# HIVE_BOARD_CHANNEL_HW.net
KiCad netlist of a schematic drawn in Altium Designer
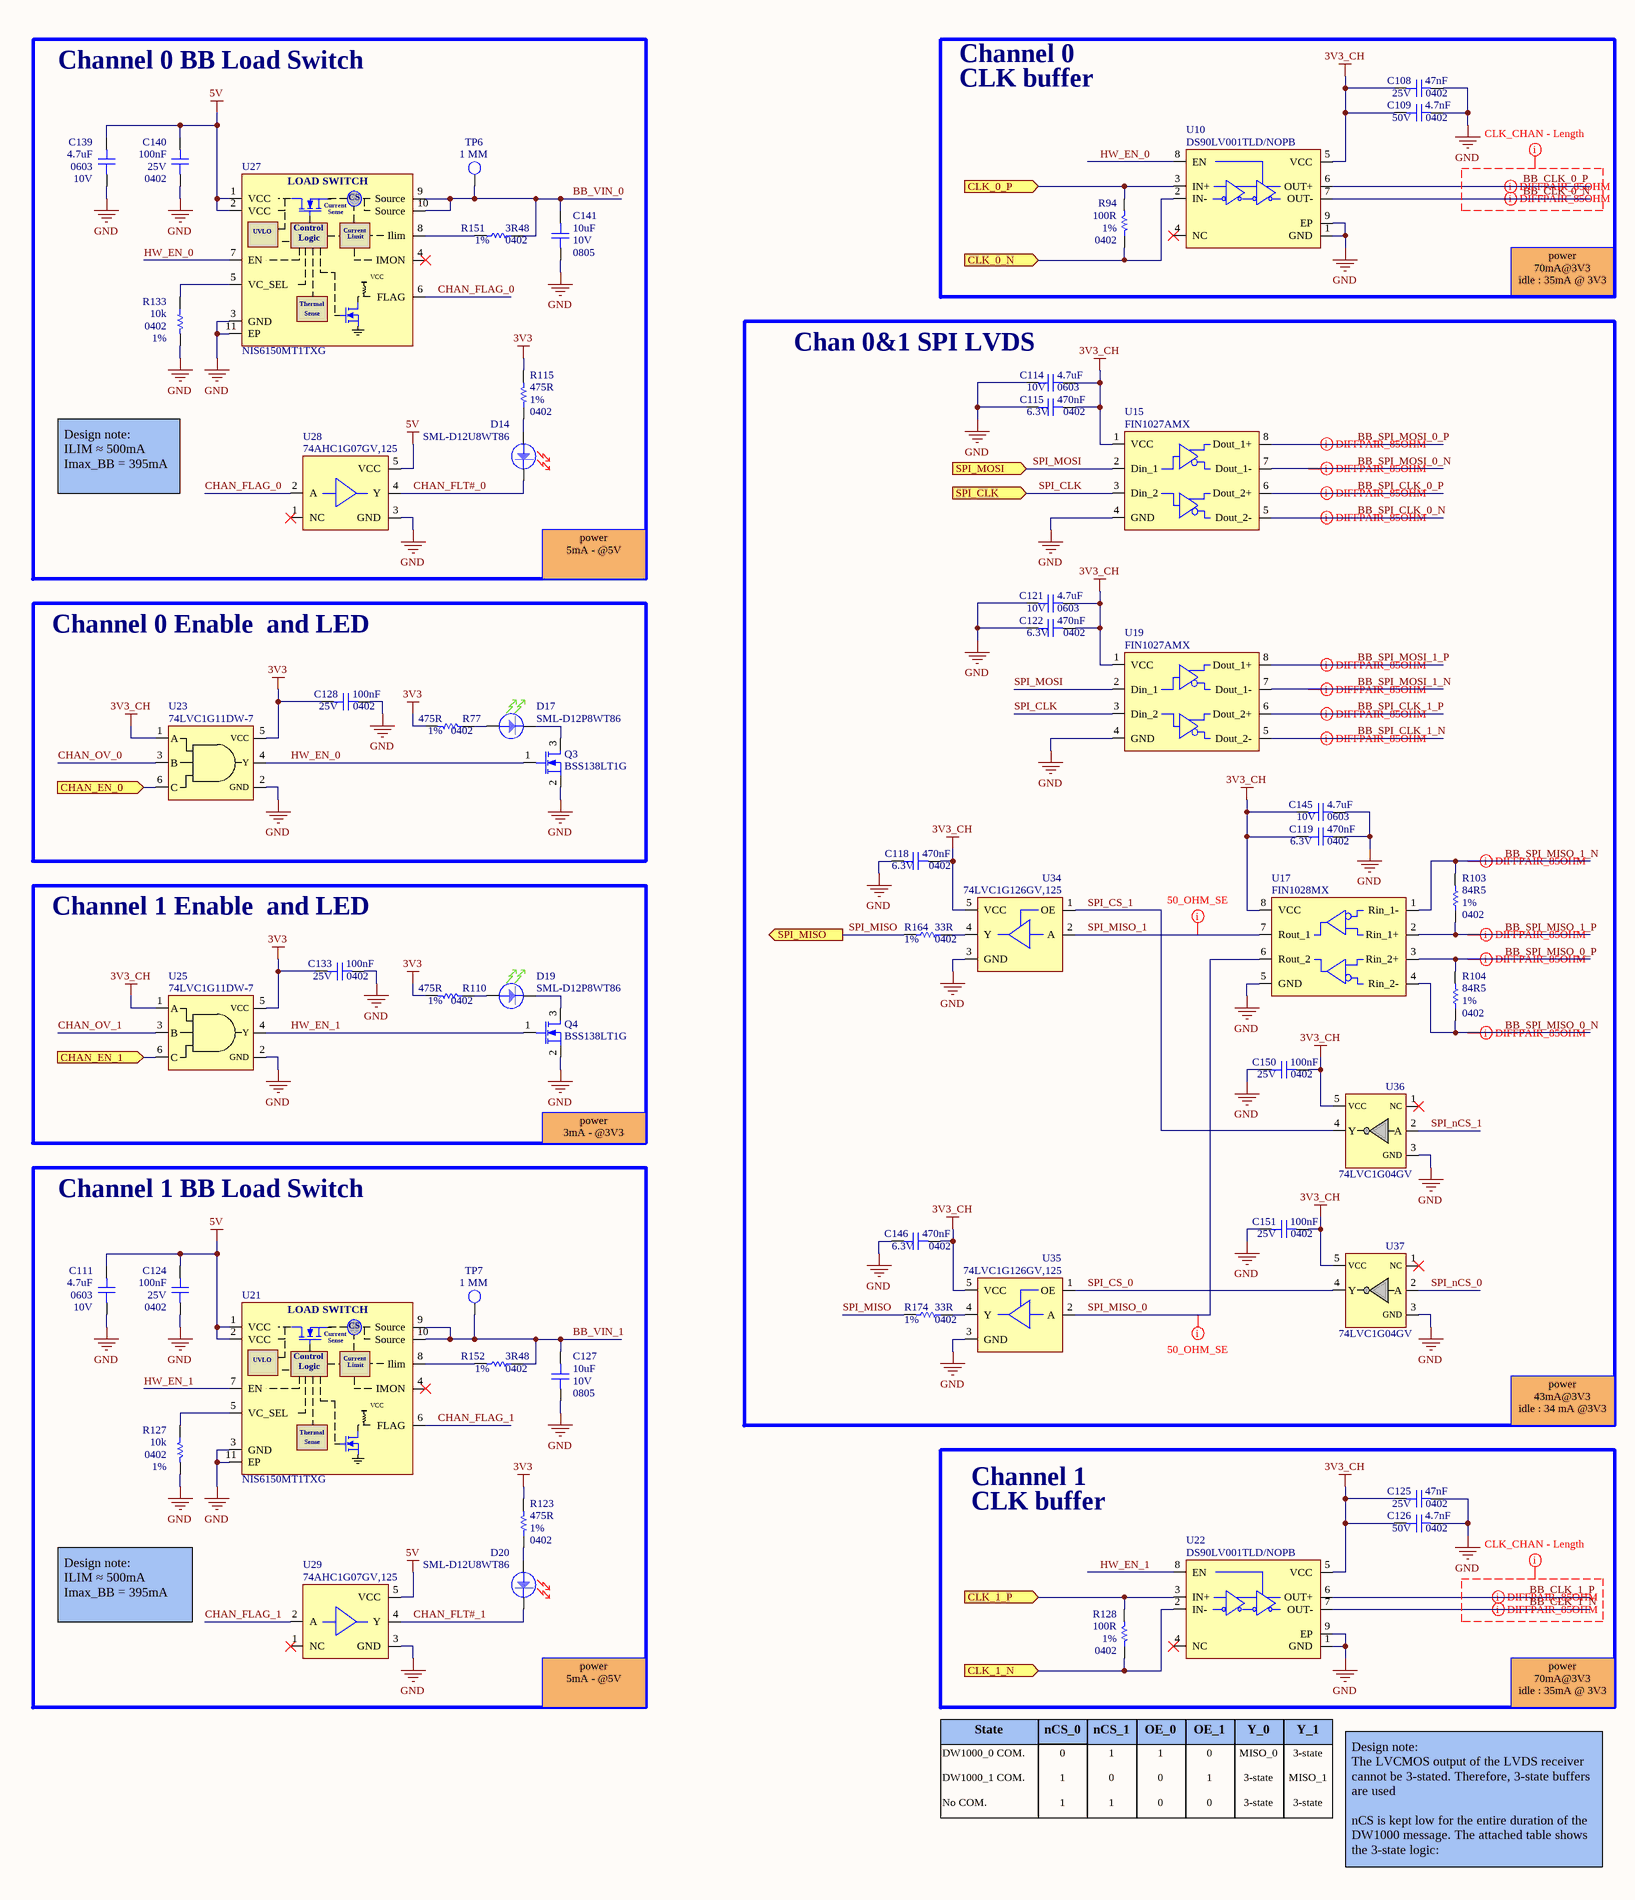
[diagram p0: HIVE_BOARD_CHANNEL_HW.SchDoc, left]
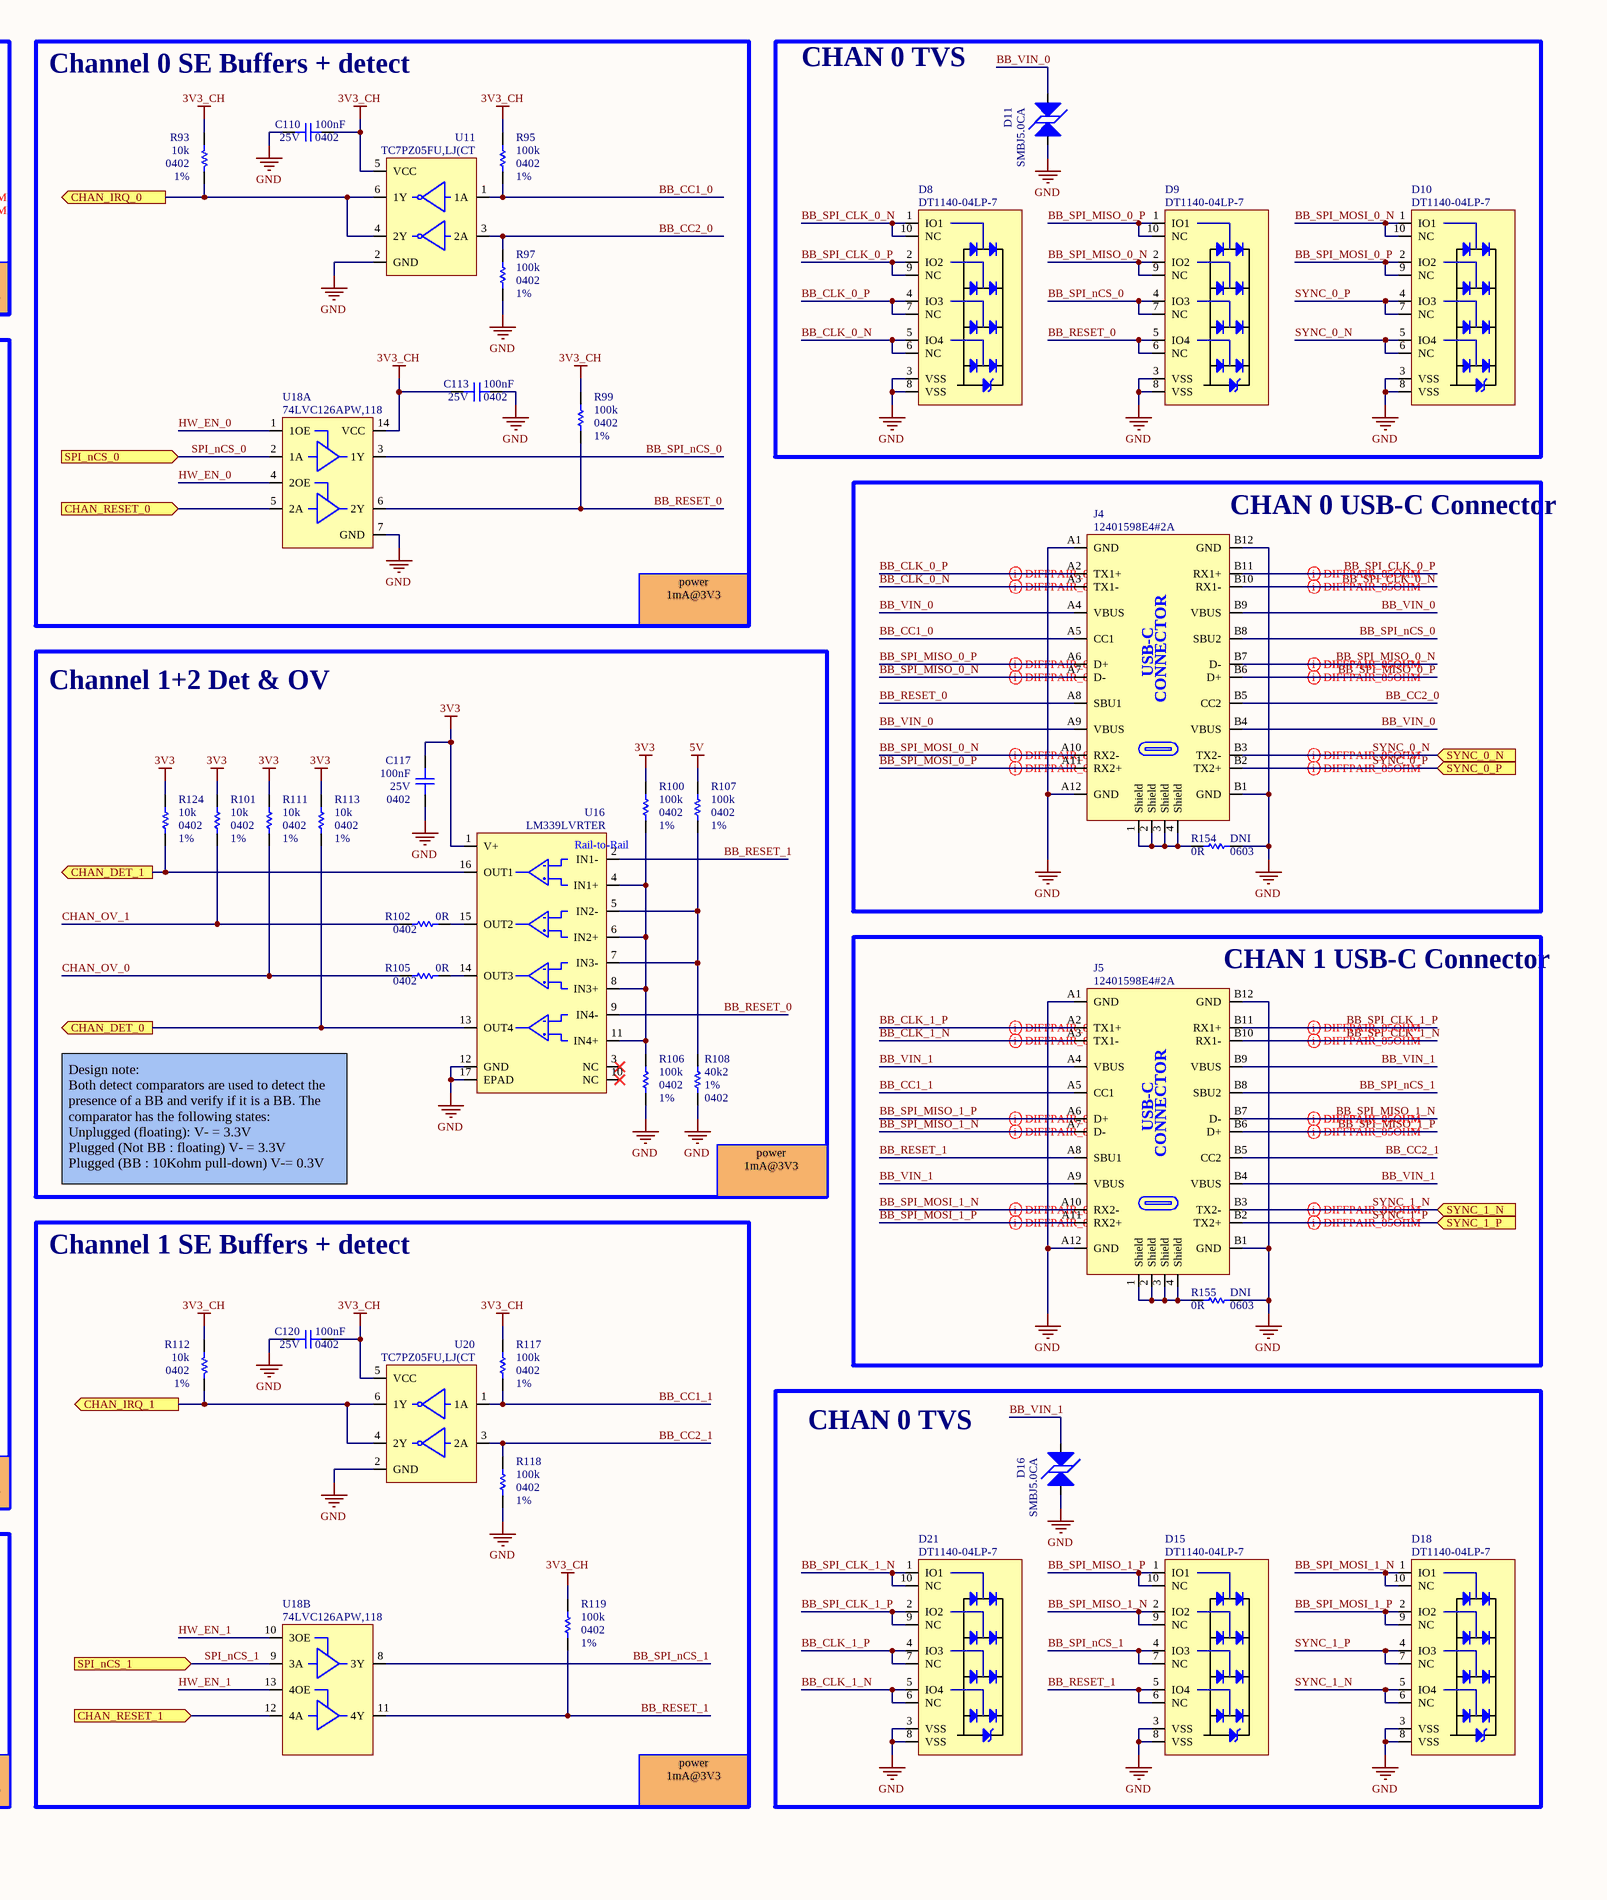
[diagram p1: HIVE_BOARD_CHANNEL_HW.SchDoc, right]

(export (version "E")
  (design (tool "Eeschema 10.0.6"))
  (components
    (comp (ref "C108")
      (value "47nF")
      (footprint "CAP_CER_0402")
      (description "CAP - CER 47nF 25V X7R - 0402")
      (fields
        (field (name "TOLERANCE") "10%")
        (field (name "PACKAGE") "0402")
        (field (name "VOLTAGE RATING") "25V")
        (field (name "Comment") "GRM155R71E473KA88J")
        (field (name "CREATEDBY/DATE") "P. Marcoux 2020-02-05")
        (field (name "VERIFIEDBY") "C.Paulin - 22/04/2020")
      )
      (libsource (lib "GRAMS_MASTER_LIB") (part "CAP_CER_GRM155R71E473KA88J"))
    )
    (comp (ref "C109")
      (value "4.7nF")
      (footprint "CAP_CER_0402")
      (description "CAP - CER 4700PF 50V X7R 0402")
      (fields
        (field (name "TOLERANCE") "±10%")
        (field (name "PACKAGE") "0402")
        (field (name "VOLTAGE RATING") "50V")
        (field (name "Comment") "CL05B472KB5VPNC")
        (field (name "CREATEDBY/DATE") "Philippe Arsenault/ 2021-03-26")
      )
      (libsource (lib "SWARMUS_LIB") (part "CAP_CER_CL05B472KB5VPNC"))
    )
    (comp (ref "C110")
      (value "100nF")
      (footprint "CAP_CER_0402")
      (description "CAP - CER 0.1µF 10% 25V X7R - 0402")
      (fields
        (field (name "TOLERANCE") "10%")
        (field (name "PACKAGE") "0402")
        (field (name "VOLTAGE RATING") "25V")
        (field (name "Comment") "CGA2B3X7R1E104K050BB")
        (field (name "CREATEDBY/DATE") "Nicolas Roy 2018-11-07")
        (field (name "VERIFIEDBY") "Nicolas V. (2019-01-22)")
      )
      (libsource (lib "GRAMS_MASTER_LIB") (part "CAP_CER_CGA2B3X7R1E104K050BB"))
    )
    (comp (ref "C111")
      (value "4.7uF")
      (footprint "CAP_CER_0603")
      (description "4.7µF ±10% 10V Ceramic Capacitor X5R 0603")
      (fields
        (field (name "TOLERANCE") "10%")
        (field (name "PACKAGE") "0603")
        (field (name "VOLTAGE RATING") "10V")
        (field (name "Comment") "CL10A475KP8NNNC")
        (field (name "CREATEDBY/DATE") "Hubert Dube - 25/02/2021")
        (field (name "VERIFIEDBY") "Philippe Arsenault/2021-03-14")
      )
      (libsource (lib "SWARMUS_LIB") (part "CAP_CER_CL10A475KP8NNNC"))
    )
    (comp (ref "C113")
      (value "100nF")
      (footprint "CAP_CER_0402")
      (description "CAP - CER 0.1µF 10% 25V X7R - 0402")
      (fields
        (field (name "TOLERANCE") "10%")
        (field (name "PACKAGE") "0402")
        (field (name "VOLTAGE RATING") "25V")
        (field (name "Comment") "CGA2B3X7R1E104K050BB")
        (field (name "CREATEDBY/DATE") "Nicolas Roy 2018-11-07")
        (field (name "VERIFIEDBY") "Nicolas V. (2019-01-22)")
      )
      (libsource (lib "GRAMS_MASTER_LIB") (part "CAP_CER_CGA2B3X7R1E104K050BB"))
    )
    (comp (ref "C114")
      (value "4.7uF")
      (footprint "CAP_CER_0603")
      (description "4.7µF ±10% 10V Ceramic Capacitor X5R 0603")
      (fields
        (field (name "TOLERANCE") "10%")
        (field (name "PACKAGE") "0603")
        (field (name "VOLTAGE RATING") "10V")
        (field (name "Comment") "CL10A475KP8NNNC")
        (field (name "CREATEDBY/DATE") "Hubert Dube - 25/02/2021")
        (field (name "VERIFIEDBY") "Philippe Arsenault/2021-03-14")
      )
      (libsource (lib "SWARMUS_LIB") (part "CAP_CER_CL10A475KP8NNNC"))
    )
    (comp (ref "C115")
      (value "470nF")
      (footprint "CAP_CER_0402")
      (description "CAP - CER 470nF 6.3V X7R - 0402")
      (fields
        (field (name "TOLERANCE") "10%")
        (field (name "PACKAGE") "0402")
        (field (name "VOLTAGE RATING") "6.3V")
        (field (name "Comment") "JMK105B7474KVHF")
        (field (name "CREATEDBY/DATE") "Nicolas (2019-06-21)")
        (field (name "VERIFIEDBY") "Nicolas V. (2019-06-21)")
      )
      (libsource (lib "GRAMS_MASTER_LIB") (part "CAP_CER_JMK105B7474KVHF"))
    )
    (comp (ref "C117")
      (value "100nF")
      (footprint "CAP_CER_0402")
      (description "CAP - CER 0.1µF 10% 25V X7R - 0402")
      (fields
        (field (name "TOLERANCE") "10%")
        (field (name "PACKAGE") "0402")
        (field (name "VOLTAGE RATING") "25V")
        (field (name "Comment") "CGA2B3X7R1E104K050BB")
        (field (name "CREATEDBY/DATE") "Nicolas Roy 2018-11-07")
        (field (name "VERIFIEDBY") "Nicolas V. (2019-01-22)")
      )
      (libsource (lib "GRAMS_MASTER_LIB") (part "CAP_CER_CGA2B3X7R1E104K050BB"))
    )
    (comp (ref "C118")
      (value "470nF")
      (footprint "CAP_CER_0402")
      (description "CAP - CER 470nF 6.3V X7R - 0402")
      (fields
        (field (name "TOLERANCE") "10%")
        (field (name "PACKAGE") "0402")
        (field (name "VOLTAGE RATING") "6.3V")
        (field (name "Comment") "JMK105B7474KVHF")
        (field (name "CREATEDBY/DATE") "Nicolas (2019-06-21)")
        (field (name "VERIFIEDBY") "Nicolas V. (2019-06-21)")
      )
      (libsource (lib "GRAMS_MASTER_LIB") (part "CAP_CER_JMK105B7474KVHF"))
    )
    (comp (ref "C119")
      (value "470nF")
      (footprint "CAP_CER_0402")
      (description "CAP - CER 470nF 6.3V X7R - 0402")
      (fields
        (field (name "TOLERANCE") "10%")
        (field (name "PACKAGE") "0402")
        (field (name "VOLTAGE RATING") "6.3V")
        (field (name "Comment") "JMK105B7474KVHF")
        (field (name "CREATEDBY/DATE") "Nicolas (2019-06-21)")
        (field (name "VERIFIEDBY") "Nicolas V. (2019-06-21)")
      )
      (libsource (lib "GRAMS_MASTER_LIB") (part "CAP_CER_JMK105B7474KVHF"))
    )
    (comp (ref "C120")
      (value "100nF")
      (footprint "CAP_CER_0402")
      (description "CAP - CER 0.1µF 10% 25V X7R - 0402")
      (fields
        (field (name "TOLERANCE") "10%")
        (field (name "PACKAGE") "0402")
        (field (name "VOLTAGE RATING") "25V")
        (field (name "Comment") "CGA2B3X7R1E104K050BB")
        (field (name "CREATEDBY/DATE") "Nicolas Roy 2018-11-07")
        (field (name "VERIFIEDBY") "Nicolas V. (2019-01-22)")
      )
      (libsource (lib "GRAMS_MASTER_LIB") (part "CAP_CER_CGA2B3X7R1E104K050BB"))
    )
    (comp (ref "C121")
      (value "4.7uF")
      (footprint "CAP_CER_0603")
      (description "4.7µF ±10% 10V Ceramic Capacitor X5R 0603")
      (fields
        (field (name "TOLERANCE") "10%")
        (field (name "PACKAGE") "0603")
        (field (name "VOLTAGE RATING") "10V")
        (field (name "Comment") "CL10A475KP8NNNC")
        (field (name "CREATEDBY/DATE") "Hubert Dube - 25/02/2021")
        (field (name "VERIFIEDBY") "Philippe Arsenault/2021-03-14")
      )
      (libsource (lib "SWARMUS_LIB") (part "CAP_CER_CL10A475KP8NNNC"))
    )
    (comp (ref "C122")
      (value "470nF")
      (footprint "CAP_CER_0402")
      (description "CAP - CER 470nF 6.3V X7R - 0402")
      (fields
        (field (name "TOLERANCE") "10%")
        (field (name "PACKAGE") "0402")
        (field (name "VOLTAGE RATING") "6.3V")
        (field (name "Comment") "JMK105B7474KVHF")
        (field (name "CREATEDBY/DATE") "Nicolas (2019-06-21)")
        (field (name "VERIFIEDBY") "Nicolas V. (2019-06-21)")
      )
      (libsource (lib "GRAMS_MASTER_LIB") (part "CAP_CER_JMK105B7474KVHF"))
    )
    (comp (ref "C124")
      (value "100nF")
      (footprint "CAP_CER_0402")
      (description "CAP - CER 0.1µF 10% 25V X7R - 0402")
      (fields
        (field (name "TOLERANCE") "10%")
        (field (name "PACKAGE") "0402")
        (field (name "VOLTAGE RATING") "25V")
        (field (name "Comment") "CGA2B3X7R1E104K050BB")
        (field (name "CREATEDBY/DATE") "Nicolas Roy 2018-11-07")
        (field (name "VERIFIEDBY") "Nicolas V. (2019-01-22)")
      )
      (libsource (lib "GRAMS_MASTER_LIB") (part "CAP_CER_CGA2B3X7R1E104K050BB"))
    )
    (comp (ref "C125")
      (value "47nF")
      (footprint "CAP_CER_0402")
      (description "CAP - CER 47nF 25V X7R - 0402")
      (fields
        (field (name "TOLERANCE") "10%")
        (field (name "PACKAGE") "0402")
        (field (name "VOLTAGE RATING") "25V")
        (field (name "Comment") "GRM155R71E473KA88J")
        (field (name "CREATEDBY/DATE") "P. Marcoux 2020-02-05")
        (field (name "VERIFIEDBY") "C.Paulin - 22/04/2020")
      )
      (libsource (lib "GRAMS_MASTER_LIB") (part "CAP_CER_GRM155R71E473KA88J"))
    )
    (comp (ref "C126")
      (value "4.7nF")
      (footprint "CAP_CER_0402")
      (description "CAP - CER 4700PF 50V X7R 0402")
      (fields
        (field (name "TOLERANCE") "±10%")
        (field (name "PACKAGE") "0402")
        (field (name "VOLTAGE RATING") "50V")
        (field (name "Comment") "CL05B472KB5VPNC")
        (field (name "CREATEDBY/DATE") "Philippe Arsenault/ 2021-03-26")
      )
      (libsource (lib "SWARMUS_LIB") (part "CAP_CER_CL05B472KB5VPNC"))
    )
    (comp (ref "C127")
      (value "10uF")
      (footprint "CAP_CER_0805")
      (description "CAP - CER 10UF 10% 10V X5R - 0805")
      (fields
        (field (name "TOLERANCE") "10%")
        (field (name "PACKAGE") "0805")
        (field (name "VOLTAGE RATING") "10V")
        (field (name "Comment") "LMK212BJ106KG-T")
        (field (name "CREATEDBY/DATE") "Caroline Paulin / 25 juillet 2018")
        (field (name "VERIFIEDBY") "Nicolas V. (2019-01-22)")
      )
      (libsource (lib "GRAMS_MASTER_LIB") (part "CAP_CER_LMK212BJ106KG-T"))
    )
    (comp (ref "C128")
      (value "100nF")
      (footprint "CAP_CER_0402")
      (description "CAP - CER 0.1µF 10% 25V X7R - 0402")
      (fields
        (field (name "TOLERANCE") "10%")
        (field (name "PACKAGE") "0402")
        (field (name "VOLTAGE RATING") "25V")
        (field (name "Comment") "CGA2B3X7R1E104K050BB")
        (field (name "CREATEDBY/DATE") "Nicolas Roy 2018-11-07")
        (field (name "VERIFIEDBY") "Nicolas V. (2019-01-22)")
      )
      (libsource (lib "GRAMS_MASTER_LIB") (part "CAP_CER_CGA2B3X7R1E104K050BB"))
    )
    (comp (ref "C133")
      (value "100nF")
      (footprint "CAP_CER_0402")
      (description "CAP - CER 0.1µF 10% 25V X7R - 0402")
      (fields
        (field (name "TOLERANCE") "10%")
        (field (name "PACKAGE") "0402")
        (field (name "VOLTAGE RATING") "25V")
        (field (name "Comment") "CGA2B3X7R1E104K050BB")
        (field (name "CREATEDBY/DATE") "Nicolas Roy 2018-11-07")
        (field (name "VERIFIEDBY") "Nicolas V. (2019-01-22)")
      )
      (libsource (lib "GRAMS_MASTER_LIB") (part "CAP_CER_CGA2B3X7R1E104K050BB"))
    )
    (comp (ref "C139")
      (value "4.7uF")
      (footprint "CAP_CER_0603")
      (description "4.7µF ±10% 10V Ceramic Capacitor X5R 0603")
      (fields
        (field (name "TOLERANCE") "10%")
        (field (name "PACKAGE") "0603")
        (field (name "VOLTAGE RATING") "10V")
        (field (name "Comment") "CL10A475KP8NNNC")
        (field (name "CREATEDBY/DATE") "Hubert Dube - 25/02/2021")
        (field (name "VERIFIEDBY") "Philippe Arsenault/2021-03-14")
      )
      (libsource (lib "SWARMUS_LIB") (part "CAP_CER_CL10A475KP8NNNC"))
    )
    (comp (ref "C140")
      (value "100nF")
      (footprint "CAP_CER_0402")
      (description "CAP - CER 0.1µF 10% 25V X7R - 0402")
      (fields
        (field (name "TOLERANCE") "10%")
        (field (name "PACKAGE") "0402")
        (field (name "VOLTAGE RATING") "25V")
        (field (name "Comment") "CGA2B3X7R1E104K050BB")
        (field (name "CREATEDBY/DATE") "Nicolas Roy 2018-11-07")
        (field (name "VERIFIEDBY") "Nicolas V. (2019-01-22)")
      )
      (libsource (lib "GRAMS_MASTER_LIB") (part "CAP_CER_CGA2B3X7R1E104K050BB"))
    )
    (comp (ref "C141")
      (value "10uF")
      (footprint "CAP_CER_0805")
      (description "CAP - CER 10UF 10% 10V X5R - 0805")
      (fields
        (field (name "TOLERANCE") "10%")
        (field (name "PACKAGE") "0805")
        (field (name "VOLTAGE RATING") "10V")
        (field (name "Comment") "LMK212BJ106KG-T")
        (field (name "CREATEDBY/DATE") "Caroline Paulin / 25 juillet 2018")
        (field (name "VERIFIEDBY") "Nicolas V. (2019-01-22)")
      )
      (libsource (lib "GRAMS_MASTER_LIB") (part "CAP_CER_LMK212BJ106KG-T"))
    )
    (comp (ref "C145")
      (value "4.7uF")
      (footprint "CAP_CER_0603")
      (description "4.7µF ±10% 10V Ceramic Capacitor X5R 0603")
      (fields
        (field (name "TOLERANCE") "10%")
        (field (name "PACKAGE") "0603")
        (field (name "VOLTAGE RATING") "10V")
        (field (name "Comment") "CL10A475KP8NNNC")
        (field (name "CREATEDBY/DATE") "Hubert Dube - 25/02/2021")
        (field (name "VERIFIEDBY") "Philippe Arsenault/2021-03-14")
      )
      (libsource (lib "SWARMUS_LIB") (part "CAP_CER_CL10A475KP8NNNC"))
    )
    (comp (ref "C146")
      (value "470nF")
      (footprint "CAP_CER_0402")
      (description "CAP - CER 470nF 6.3V X7R - 0402")
      (fields
        (field (name "TOLERANCE") "10%")
        (field (name "PACKAGE") "0402")
        (field (name "VOLTAGE RATING") "6.3V")
        (field (name "Comment") "JMK105B7474KVHF")
        (field (name "CREATEDBY/DATE") "Nicolas (2019-06-21)")
        (field (name "VERIFIEDBY") "Nicolas V. (2019-06-21)")
      )
      (libsource (lib "GRAMS_MASTER_LIB") (part "CAP_CER_JMK105B7474KVHF"))
    )
    (comp (ref "C150")
      (value "100nF")
      (footprint "CAP_CER_0402")
      (description "CAP - CER 0.1µF 10% 25V X7R - 0402")
      (fields
        (field (name "TOLERANCE") "10%")
        (field (name "PACKAGE") "0402")
        (field (name "VOLTAGE RATING") "25V")
        (field (name "Comment") "CGA2B3X7R1E104K050BB")
        (field (name "CREATEDBY/DATE") "Nicolas Roy 2018-11-07")
        (field (name "VERIFIEDBY") "Nicolas V. (2019-01-22)")
      )
      (libsource (lib "GRAMS_MASTER_LIB") (part "CAP_CER_CGA2B3X7R1E104K050BB"))
    )
    (comp (ref "C151")
      (value "100nF")
      (footprint "CAP_CER_0402")
      (description "CAP - CER 0.1µF 10% 25V X7R - 0402")
      (fields
        (field (name "TOLERANCE") "10%")
        (field (name "PACKAGE") "0402")
        (field (name "VOLTAGE RATING") "25V")
        (field (name "Comment") "CGA2B3X7R1E104K050BB")
        (field (name "CREATEDBY/DATE") "Nicolas Roy 2018-11-07")
        (field (name "VERIFIEDBY") "Nicolas V. (2019-01-22)")
      )
      (libsource (lib "GRAMS_MASTER_LIB") (part "CAP_CER_CGA2B3X7R1E104K050BB"))
    )
    (comp (ref "D8")
      (value "DT1140-04LP-7")
      (footprint "TVS_DATA_DT1140-04LP-7")
      (description "TVS - DIODE 5.5V 10V - 10-UFDFN")
      (fields
        (field (name "CREATEDBY/DATE") "Joël Lemay 2019-11-20")
        (field (name "VERIFIEDBY") "C.Paulin - 21/11/2019")
      )
      (libsource (lib "GRAMS_MASTER_LIB") (part "TVS_DATA_DT1140-04LP-7"))
    )
    (comp (ref "D9")
      (value "DT1140-04LP-7")
      (footprint "TVS_DATA_DT1140-04LP-7")
      (description "TVS - DIODE 5.5V 10V - 10-UFDFN")
      (fields
        (field (name "CREATEDBY/DATE") "Joël Lemay 2019-11-20")
        (field (name "VERIFIEDBY") "C.Paulin - 21/11/2019")
      )
      (libsource (lib "GRAMS_MASTER_LIB") (part "TVS_DATA_DT1140-04LP-7"))
    )
    (comp (ref "D10")
      (value "DT1140-04LP-7")
      (footprint "TVS_DATA_DT1140-04LP-7")
      (description "TVS - DIODE 5.5V 10V - 10-UFDFN")
      (fields
        (field (name "CREATEDBY/DATE") "Joël Lemay 2019-11-20")
        (field (name "VERIFIEDBY") "C.Paulin - 21/11/2019")
      )
      (libsource (lib "GRAMS_MASTER_LIB") (part "TVS_DATA_DT1140-04LP-7"))
    )
    (comp (ref "D11")
      (value "SMBJ5.0CA")
      (footprint "TVS_PWR_SMBJ5.0CA")
      (description "TVS - BIDIR 5V 9.2V 600W - DO214AA")
      (fields
        (field (name "CREATEDBY/DATE") "Jonathan Bouchard - 2019-03-22")
        (field (name "VERIFIEDBY") "Nicolas V. (2019-05-06)")
      )
      (libsource (lib "GRAMS_MASTER_LIB") (part "TVS_PWR_SMBJ5.0CA"))
    )
    (comp (ref "D14")
      (value "SML-D12U8WT86")
      (footprint "LED_SML-D12U8WT86")
      (description "LED - RED DIFFUSED 0603 SMD - 0603")
      (fields
        (field (name "CREATEDBY/DATE") "Olivier Bernard / 01/02/2018")
        (field (name "VERIFIEDBY") "Caroline Paulin / 6 juillet 2018")
      )
      (libsource (lib "GRAMS_MASTER_LIB") (part "LED_SML-D12U8WT86"))
    )
    (comp (ref "D15")
      (value "DT1140-04LP-7")
      (footprint "TVS_DATA_DT1140-04LP-7")
      (description "TVS - DIODE 5.5V 10V - 10-UFDFN")
      (fields
        (field (name "CREATEDBY/DATE") "Joël Lemay 2019-11-20")
        (field (name "VERIFIEDBY") "C.Paulin - 21/11/2019")
      )
      (libsource (lib "GRAMS_MASTER_LIB") (part "TVS_DATA_DT1140-04LP-7"))
    )
    (comp (ref "D16")
      (value "SMBJ5.0CA")
      (footprint "TVS_PWR_SMBJ5.0CA")
      (description "TVS - BIDIR 5V 9.2V 600W - DO214AA")
      (fields
        (field (name "CREATEDBY/DATE") "Jonathan Bouchard - 2019-03-22")
        (field (name "VERIFIEDBY") "Nicolas V. (2019-05-06)")
      )
      (libsource (lib "GRAMS_MASTER_LIB") (part "TVS_PWR_SMBJ5.0CA"))
    )
    (comp (ref "D17")
      (value "SML-D12P8WT86")
      (footprint "LED_SML-D12P8WT86")
      (description "LED - GREEN DIFFUSED 0603 SMD - 0603")
      (fields
        (field (name "CREATEDBY/DATE") "Keven Deslandes - 2018/11/21")
        (field (name "VERIFIEDBY") "Caroline Paulin - 13 février 2019")
      )
      (libsource (lib "GRAMS_MASTER_LIB") (part "LED_SML-D12P8WT86"))
    )
    (comp (ref "D18")
      (value "DT1140-04LP-7")
      (footprint "TVS_DATA_DT1140-04LP-7")
      (description "TVS - DIODE 5.5V 10V - 10-UFDFN")
      (fields
        (field (name "CREATEDBY/DATE") "Joël Lemay 2019-11-20")
        (field (name "VERIFIEDBY") "C.Paulin - 21/11/2019")
      )
      (libsource (lib "GRAMS_MASTER_LIB") (part "TVS_DATA_DT1140-04LP-7"))
    )
    (comp (ref "D19")
      (value "SML-D12P8WT86")
      (footprint "LED_SML-D12P8WT86")
      (description "LED - GREEN DIFFUSED 0603 SMD - 0603")
      (fields
        (field (name "CREATEDBY/DATE") "Keven Deslandes - 2018/11/21")
        (field (name "VERIFIEDBY") "Caroline Paulin - 13 février 2019")
      )
      (libsource (lib "GRAMS_MASTER_LIB") (part "LED_SML-D12P8WT86"))
    )
    (comp (ref "D20")
      (value "SML-D12U8WT86")
      (footprint "LED_SML-D12U8WT86")
      (description "LED - RED DIFFUSED 0603 SMD - 0603")
      (fields
        (field (name "CREATEDBY/DATE") "Olivier Bernard / 01/02/2018")
        (field (name "VERIFIEDBY") "Caroline Paulin / 6 juillet 2018")
      )
      (libsource (lib "GRAMS_MASTER_LIB") (part "LED_SML-D12U8WT86"))
    )
    (comp (ref "D21")
      (value "DT1140-04LP-7")
      (footprint "TVS_DATA_DT1140-04LP-7")
      (description "TVS - DIODE 5.5V 10V - 10-UFDFN")
      (fields
        (field (name "CREATEDBY/DATE") "Joël Lemay 2019-11-20")
        (field (name "VERIFIEDBY") "C.Paulin - 21/11/2019")
      )
      (libsource (lib "GRAMS_MASTER_LIB") (part "TVS_DATA_DT1140-04LP-7"))
    )
    (comp (ref "J4")
      (value "12401598E4#2A")
      (footprint "CON_USB_3.2_TypeC_12401598E4#2A")
      (description "CON_USB - USB 3.2 Gen 2 (USB 3.1 Gen 2, Superspeed + (USB 3.1)) 24 pos Receptacle - R/A")
      (fields
        (field (name "CREATEDBY/DATE") "Louis-Daniel Gaulin / 07-04-2021")
        (field (name "VERIFIEDBY") "Philippe Arsenault/2021-04-08")
      )
      (libsource (lib "SWARMUS_LIB") (part "CON_USB_3.2_TypeC_12401598E4#2A"))
    )
    (comp (ref "J5")
      (value "12401598E4#2A")
      (footprint "CON_USB_3.2_TypeC_12401598E4#2A")
      (description "CON_USB - USB 3.2 Gen 2 (USB 3.1 Gen 2, Superspeed + (USB 3.1)) 24 pos Receptacle - R/A")
      (fields
        (field (name "CREATEDBY/DATE") "Louis-Daniel Gaulin / 07-04-2021")
        (field (name "VERIFIEDBY") "Philippe Arsenault/2021-04-08")
      )
      (libsource (lib "SWARMUS_LIB") (part "CON_USB_3.2_TypeC_12401598E4#2A"))
    )
    (comp (ref "Q3")
      (value "BSS138LT1G")
      (footprint "TRX_NMOS_BSS138LT1G")
      (description "TRX - NMOS - 50V 200MA - SOT−23-3")
      (fields
        (field (name "CREATEDBY/DATE") "Joel Lemay 2018-06-15")
        (field (name "VERIFIEDBY") "Caroline Paulin - 6 sept 2018")
      )
      (libsource (lib "GRAMS_MASTER_LIB") (part "TRX_NMOS_BSS138LT1G"))
    )
    (comp (ref "Q4")
      (value "BSS138LT1G")
      (footprint "TRX_NMOS_BSS138LT1G")
      (description "TRX - NMOS - 50V 200MA - SOT−23-3")
      (fields
        (field (name "CREATEDBY/DATE") "Joel Lemay 2018-06-15")
        (field (name "VERIFIEDBY") "Caroline Paulin - 6 sept 2018")
      )
      (libsource (lib "GRAMS_MASTER_LIB") (part "TRX_NMOS_BSS138LT1G"))
    )
    (comp (ref "R77")
      (value "475R")
      (footprint "RES_0402")
      (description "RES - 475R 1% 1/10W- 0402")
      (fields
        (field (name "TOLERANCE") "1%")
        (field (name "PACKAGE") "0402")
        (field (name "Comment") "ERJ-2RKF4750X")
        (field (name "CREATEDBY/DATE") "Keven Deslandes 2018-10-17")
        (field (name "VERIFIEDBY") "Carolilne Paulin - 18/12/2018")
      )
      (libsource (lib "GRAMS_MASTER_LIB") (part "RES_ERJ-2RKF4750X"))
    )
    (comp (ref "R93")
      (value "10k")
      (footprint "RES_0402")
      (description "RES - 10K OHMS 1% 1/16W - 0402")
      (fields
        (field (name "TOLERANCE") "1%")
        (field (name "PACKAGE") "0402")
        (field (name "Comment") "RC0402FR-0710KL")
        (field (name "CREATEDBY/DATE") "Nicolas V. (2018-11-20)")
        (field (name "VERIFIEDBY") "Nicolas V. (2018-11-20)")
      )
      (libsource (lib "GRAMS_MASTER_LIB") (part "RES_RC0402FR-0710KL"))
    )
    (comp (ref "R94")
      (value "100R")
      (footprint "RES_0402")
      (description "RES - 100R OHM 1% 1/16W - 0402")
      (fields
        (field (name "TOLERANCE") "1%")
        (field (name "PACKAGE") "0402")
        (field (name "Comment") "RC0402FR-07100RP")
        (field (name "CREATEDBY/DATE") "Jonathan Bouchard 2018-07-05")
        (field (name "VERIFIEDBY") "Arnaud Samson 16-07-18")
      )
      (libsource (lib "GRAMS_MASTER_LIB") (part "RES_RC0402FR-07100RP"))
    )
    (comp (ref "R95")
      (value "100k")
      (footprint "RES_0402")
      (description "RES - 100K 1% 1/16W - 0402")
      (fields
        (field (name "TOLERANCE") "1%")
        (field (name "PACKAGE") "0402")
        (field (name "Comment") "RC0402FR-07100KL")
        (field (name "CREATEDBY/DATE") "Keven Deslandes 2018-10-19")
        (field (name "VERIFIEDBY") "Caroline Paulin - 18/12/2018")
      )
      (libsource (lib "GRAMS_MASTER_LIB") (part "RES_RC0402FR-07100KL"))
    )
    (comp (ref "R97")
      (value "100k")
      (footprint "RES_0402")
      (description "RES - 100K 1% 1/16W - 0402")
      (fields
        (field (name "TOLERANCE") "1%")
        (field (name "PACKAGE") "0402")
        (field (name "Comment") "RC0402FR-07100KL")
        (field (name "CREATEDBY/DATE") "Keven Deslandes 2018-10-19")
        (field (name "VERIFIEDBY") "Caroline Paulin - 18/12/2018")
      )
      (libsource (lib "GRAMS_MASTER_LIB") (part "RES_RC0402FR-07100KL"))
    )
    (comp (ref "R99")
      (value "100k")
      (footprint "RES_0402")
      (description "RES - 100K 1% 1/16W - 0402")
      (fields
        (field (name "TOLERANCE") "1%")
        (field (name "PACKAGE") "0402")
        (field (name "Comment") "RC0402FR-07100KL")
        (field (name "CREATEDBY/DATE") "Keven Deslandes 2018-10-19")
        (field (name "VERIFIEDBY") "Caroline Paulin - 18/12/2018")
      )
      (libsource (lib "GRAMS_MASTER_LIB") (part "RES_RC0402FR-07100KL"))
    )
    (comp (ref "R100")
      (value "100k")
      (footprint "RES_0402")
      (description "RES - 100K 1% 1/16W - 0402")
      (fields
        (field (name "TOLERANCE") "1%")
        (field (name "PACKAGE") "0402")
        (field (name "Comment") "RC0402FR-07100KL")
        (field (name "CREATEDBY/DATE") "Keven Deslandes 2018-10-19")
        (field (name "VERIFIEDBY") "Caroline Paulin - 18/12/2018")
      )
      (libsource (lib "GRAMS_MASTER_LIB") (part "RES_RC0402FR-07100KL"))
    )
    (comp (ref "R101")
      (value "10k")
      (footprint "RES_0402")
      (description "RES - 10K OHMS 1% 1/16W - 0402")
      (fields
        (field (name "TOLERANCE") "1%")
        (field (name "PACKAGE") "0402")
        (field (name "Comment") "RC0402FR-0710KL")
        (field (name "CREATEDBY/DATE") "Nicolas V. (2018-11-20)")
        (field (name "VERIFIEDBY") "Nicolas V. (2018-11-20)")
      )
      (libsource (lib "GRAMS_MASTER_LIB") (part "RES_RC0402FR-0710KL"))
    )
    (comp (ref "R102")
      (value "0R")
      (footprint "RES_0402")
      (description "RES - 0R 1/16W 1A  - 0402")
      (fields
        (field (name "PACKAGE") "0402")
        (field (name "Comment") "RC0402FR-070RL")
        (field (name "CREATEDBY/DATE") "Keven Deslandes 2018-09-12")
        (field (name "VERIFIEDBY") "Caroline Paulin - 27 fév 2019")
      )
      (libsource (lib "GRAMS_MASTER_LIB") (part "RES_RC0402FR-070RL"))
    )
    (comp (ref "R103")
      (value "84R5")
      (footprint "RES_0402")
      (description "RES - 84R5 1% 1/16W - 0402")
      (fields
        (field (name "TOLERANCE") "1%")
        (field (name "PACKAGE") "0402")
        (field (name "Comment") "RC0402FR-0784R5L")
        (field (name "CREATEDBY/DATE") "Philippe Arsenault/ 2021-03-31")
      )
      (libsource (lib "SWARMUS_LIB") (part "RES_RC0402FR-0784R5L"))
    )
    (comp (ref "R104")
      (value "84R5")
      (footprint "RES_0402")
      (description "RES - 84R5 1% 1/16W - 0402")
      (fields
        (field (name "TOLERANCE") "1%")
        (field (name "PACKAGE") "0402")
        (field (name "Comment") "RC0402FR-0784R5L")
        (field (name "CREATEDBY/DATE") "Philippe Arsenault/ 2021-03-31")
      )
      (libsource (lib "SWARMUS_LIB") (part "RES_RC0402FR-0784R5L"))
    )
    (comp (ref "R105")
      (value "0R")
      (footprint "RES_0402")
      (description "RES - 0R 1/16W 1A  - 0402")
      (fields
        (field (name "PACKAGE") "0402")
        (field (name "Comment") "RC0402FR-070RL")
        (field (name "CREATEDBY/DATE") "Keven Deslandes 2018-09-12")
        (field (name "VERIFIEDBY") "Caroline Paulin - 27 fév 2019")
      )
      (libsource (lib "GRAMS_MASTER_LIB") (part "RES_RC0402FR-070RL"))
    )
    (comp (ref "R106")
      (value "100k")
      (footprint "RES_0402")
      (description "RES - 100K 1% 1/16W - 0402")
      (fields
        (field (name "TOLERANCE") "1%")
        (field (name "PACKAGE") "0402")
        (field (name "Comment") "RC0402FR-07100KL")
        (field (name "CREATEDBY/DATE") "Keven Deslandes 2018-10-19")
        (field (name "VERIFIEDBY") "Caroline Paulin - 18/12/2018")
      )
      (libsource (lib "GRAMS_MASTER_LIB") (part "RES_RC0402FR-07100KL"))
    )
    (comp (ref "R107")
      (value "100k")
      (footprint "RES_0402")
      (description "RES - 100K 1% 1/16W - 0402")
      (fields
        (field (name "TOLERANCE") "1%")
        (field (name "PACKAGE") "0402")
        (field (name "Comment") "RC0402FR-07100KL")
        (field (name "CREATEDBY/DATE") "Keven Deslandes 2018-10-19")
        (field (name "VERIFIEDBY") "Caroline Paulin - 18/12/2018")
      )
      (libsource (lib "GRAMS_MASTER_LIB") (part "RES_RC0402FR-07100KL"))
    )
    (comp (ref "R108")
      (value "40k2")
      (footprint "RES_0402")
      (description "RES - 40.2K 1% 1/16W - 0402")
      (fields
        (field (name "TOLERANCE") "1%")
        (field (name "PACKAGE") "0402")
        (field (name "Comment") "RC0402FR-0740K2L")
        (field (name "CREATEDBY/DATE") "Raphael Bouchard - 2019-08-09")
        (field (name "VERIFIEDBY") "C.Paulin - 15/08/2019")
      )
      (libsource (lib "GRAMS_MASTER_LIB") (part "RES_RC0402FR-0740K2L"))
    )
    (comp (ref "R110")
      (value "475R")
      (footprint "RES_0402")
      (description "RES - 475R 1% 1/10W- 0402")
      (fields
        (field (name "TOLERANCE") "1%")
        (field (name "PACKAGE") "0402")
        (field (name "Comment") "ERJ-2RKF4750X")
        (field (name "CREATEDBY/DATE") "Keven Deslandes 2018-10-17")
        (field (name "VERIFIEDBY") "Carolilne Paulin - 18/12/2018")
      )
      (libsource (lib "GRAMS_MASTER_LIB") (part "RES_ERJ-2RKF4750X"))
    )
    (comp (ref "R111")
      (value "10k")
      (footprint "RES_0402")
      (description "RES - 10K OHMS 1% 1/16W - 0402")
      (fields
        (field (name "TOLERANCE") "1%")
        (field (name "PACKAGE") "0402")
        (field (name "Comment") "RC0402FR-0710KL")
        (field (name "CREATEDBY/DATE") "Nicolas V. (2018-11-20)")
        (field (name "VERIFIEDBY") "Nicolas V. (2018-11-20)")
      )
      (libsource (lib "GRAMS_MASTER_LIB") (part "RES_RC0402FR-0710KL"))
    )
    (comp (ref "R112")
      (value "10k")
      (footprint "RES_0402")
      (description "RES - 10K OHMS 1% 1/16W - 0402")
      (fields
        (field (name "TOLERANCE") "1%")
        (field (name "PACKAGE") "0402")
        (field (name "Comment") "RC0402FR-0710KL")
        (field (name "CREATEDBY/DATE") "Nicolas V. (2018-11-20)")
        (field (name "VERIFIEDBY") "Nicolas V. (2018-11-20)")
      )
      (libsource (lib "GRAMS_MASTER_LIB") (part "RES_RC0402FR-0710KL"))
    )
    (comp (ref "R113")
      (value "10k")
      (footprint "RES_0402")
      (description "RES - 10K OHMS 1% 1/16W - 0402")
      (fields
        (field (name "TOLERANCE") "1%")
        (field (name "PACKAGE") "0402")
        (field (name "Comment") "RC0402FR-0710KL")
        (field (name "CREATEDBY/DATE") "Nicolas V. (2018-11-20)")
        (field (name "VERIFIEDBY") "Nicolas V. (2018-11-20)")
      )
      (libsource (lib "GRAMS_MASTER_LIB") (part "RES_RC0402FR-0710KL"))
    )
    (comp (ref "R115")
      (value "475R")
      (footprint "RES_0402")
      (description "RES - 475R 1% 1/10W- 0402")
      (fields
        (field (name "TOLERANCE") "1%")
        (field (name "PACKAGE") "0402")
        (field (name "Comment") "ERJ-2RKF4750X")
        (field (name "CREATEDBY/DATE") "Keven Deslandes 2018-10-17")
        (field (name "VERIFIEDBY") "Carolilne Paulin - 18/12/2018")
      )
      (libsource (lib "GRAMS_MASTER_LIB") (part "RES_ERJ-2RKF4750X"))
    )
    (comp (ref "R117")
      (value "100k")
      (footprint "RES_0402")
      (description "RES - 100K 1% 1/16W - 0402")
      (fields
        (field (name "TOLERANCE") "1%")
        (field (name "PACKAGE") "0402")
        (field (name "Comment") "RC0402FR-07100KL")
        (field (name "CREATEDBY/DATE") "Keven Deslandes 2018-10-19")
        (field (name "VERIFIEDBY") "Caroline Paulin - 18/12/2018")
      )
      (libsource (lib "GRAMS_MASTER_LIB") (part "RES_RC0402FR-07100KL"))
    )
    (comp (ref "R118")
      (value "100k")
      (footprint "RES_0402")
      (description "RES - 100K 1% 1/16W - 0402")
      (fields
        (field (name "TOLERANCE") "1%")
        (field (name "PACKAGE") "0402")
        (field (name "Comment") "RC0402FR-07100KL")
        (field (name "CREATEDBY/DATE") "Keven Deslandes 2018-10-19")
        (field (name "VERIFIEDBY") "Caroline Paulin - 18/12/2018")
      )
      (libsource (lib "GRAMS_MASTER_LIB") (part "RES_RC0402FR-07100KL"))
    )
    (comp (ref "R119")
      (value "100k")
      (footprint "RES_0402")
      (description "RES - 100K 1% 1/16W - 0402")
      (fields
        (field (name "TOLERANCE") "1%")
        (field (name "PACKAGE") "0402")
        (field (name "Comment") "RC0402FR-07100KL")
        (field (name "CREATEDBY/DATE") "Keven Deslandes 2018-10-19")
        (field (name "VERIFIEDBY") "Caroline Paulin - 18/12/2018")
      )
      (libsource (lib "GRAMS_MASTER_LIB") (part "RES_RC0402FR-07100KL"))
    )
    (comp (ref "R123")
      (value "475R")
      (footprint "RES_0402")
      (description "RES - 475R 1% 1/10W- 0402")
      (fields
        (field (name "TOLERANCE") "1%")
        (field (name "PACKAGE") "0402")
        (field (name "Comment") "ERJ-2RKF4750X")
        (field (name "CREATEDBY/DATE") "Keven Deslandes 2018-10-17")
        (field (name "VERIFIEDBY") "Carolilne Paulin - 18/12/2018")
      )
      (libsource (lib "GRAMS_MASTER_LIB") (part "RES_ERJ-2RKF4750X"))
    )
    (comp (ref "R124")
      (value "10k")
      (footprint "RES_0402")
      (description "RES - 10K OHMS 1% 1/16W - 0402")
      (fields
        (field (name "TOLERANCE") "1%")
        (field (name "PACKAGE") "0402")
        (field (name "Comment") "RC0402FR-0710KL")
        (field (name "CREATEDBY/DATE") "Nicolas V. (2018-11-20)")
        (field (name "VERIFIEDBY") "Nicolas V. (2018-11-20)")
      )
      (libsource (lib "GRAMS_MASTER_LIB") (part "RES_RC0402FR-0710KL"))
    )
    (comp (ref "R127")
      (value "10k")
      (footprint "RES_0402")
      (description "RES - 10K OHMS 1% 1/16W - 0402")
      (fields
        (field (name "TOLERANCE") "1%")
        (field (name "PACKAGE") "0402")
        (field (name "Comment") "RC0402FR-0710KL")
        (field (name "CREATEDBY/DATE") "Nicolas V. (2018-11-20)")
        (field (name "VERIFIEDBY") "Nicolas V. (2018-11-20)")
      )
      (libsource (lib "GRAMS_MASTER_LIB") (part "RES_RC0402FR-0710KL"))
    )
    (comp (ref "R128")
      (value "100R")
      (footprint "RES_0402")
      (description "RES - 100R OHM 1% 1/16W - 0402")
      (fields
        (field (name "TOLERANCE") "1%")
        (field (name "PACKAGE") "0402")
        (field (name "Comment") "RC0402FR-07100RP")
        (field (name "CREATEDBY/DATE") "Jonathan Bouchard 2018-07-05")
        (field (name "VERIFIEDBY") "Arnaud Samson 16-07-18")
      )
      (libsource (lib "GRAMS_MASTER_LIB") (part "RES_RC0402FR-07100RP"))
    )
    (comp (ref "R133")
      (value "10k")
      (footprint "RES_0402")
      (description "RES - 10K OHMS 1% 1/16W - 0402")
      (fields
        (field (name "TOLERANCE") "1%")
        (field (name "PACKAGE") "0402")
        (field (name "Comment") "RC0402FR-0710KL")
        (field (name "CREATEDBY/DATE") "Nicolas V. (2018-11-20)")
        (field (name "VERIFIEDBY") "Nicolas V. (2018-11-20)")
      )
      (libsource (lib "GRAMS_MASTER_LIB") (part "RES_RC0402FR-0710KL"))
    )
    (comp (ref "R151")
      (value "3R48")
      (footprint "RES_0402")
      (description "RES - 3.48 R ±1% 1/16W -  0402")
      (fields
        (field (name "TOLERANCE") "1%")
        (field (name "PACKAGE") "0402")
        (field (name "Comment") "CRCW04023R48FKED")
        (field (name "CREATEDBY/DATE") "Louis-Daniel Gaulin / 2021-05-01")
        (field (name "VERIFIEDBY") "Philippe Arsenault/2021-05-10")
      )
      (libsource (lib "SWARMUS_LIB") (part "RES_CRCW04023R48FKED"))
    )
    (comp (ref "R152")
      (value "3R48")
      (footprint "RES_0402")
      (description "RES - 3.48 R ±1% 1/16W -  0402")
      (fields
        (field (name "TOLERANCE") "1%")
        (field (name "PACKAGE") "0402")
        (field (name "Comment") "CRCW04023R48FKED")
        (field (name "CREATEDBY/DATE") "Louis-Daniel Gaulin / 2021-05-01")
        (field (name "VERIFIEDBY") "Philippe Arsenault/2021-05-10")
      )
      (libsource (lib "SWARMUS_LIB") (part "RES_CRCW04023R48FKED"))
    )
    (comp (ref "R154")
      (value "0R")
      (footprint "RES_0603")
      (description "RES - 0 ohm jumper 1/10W - 0603")
      (fields
        (field (name "ASSEMBLY NOTE") "DNI")
        (field (name "PACKAGE") "0603")
        (field (name "Comment") "RC0603JR-070RL")
        (field (name "CREATEDBY/DATE") "L-P Gauthier 2018-10-30")
        (field (name "VERIFIEDBY") "Caroline Paulin  - 5/11/2018")
      )
      (libsource (lib "GRAMS_MASTER_LIB") (part "RES_RC0603JR-070RL"))
    )
    (comp (ref "R155")
      (value "0R")
      (footprint "RES_0603")
      (description "RES - 0 ohm jumper 1/10W - 0603")
      (fields
        (field (name "ASSEMBLY NOTE") "DNI")
        (field (name "PACKAGE") "0603")
        (field (name "Comment") "RC0603JR-070RL")
        (field (name "CREATEDBY/DATE") "L-P Gauthier 2018-10-30")
        (field (name "VERIFIEDBY") "Caroline Paulin  - 5/11/2018")
      )
      (libsource (lib "GRAMS_MASTER_LIB") (part "RES_RC0603JR-070RL"))
    )
    (comp (ref "R164")
      (value "33R")
      (footprint "RES_0402")
      (description "RES - 33 OHM 1% 1/16W - 0402")
      (fields
        (field (name "TOLERANCE") "1%")
        (field (name "PACKAGE") "0402")
        (field (name "Comment") "RC0402FR-0733RL")
        (field (name "CREATEDBY/DATE") "Louis-Daniel Gaulin/ 14/01/2020")
        (field (name "VERIFIEDBY") "C.Paulin - 21/01/2020")
      )
      (libsource (lib "GRAMS_MASTER_LIB") (part "RES_RC0402FR-0733RL"))
    )
    (comp (ref "R174")
      (value "33R")
      (footprint "RES_0402")
      (description "RES - 33 OHM 1% 1/16W - 0402")
      (fields
        (field (name "TOLERANCE") "1%")
        (field (name "PACKAGE") "0402")
        (field (name "Comment") "RC0402FR-0733RL")
        (field (name "CREATEDBY/DATE") "Louis-Daniel Gaulin/ 14/01/2020")
        (field (name "VERIFIEDBY") "C.Paulin - 21/01/2020")
      )
      (libsource (lib "GRAMS_MASTER_LIB") (part "RES_RC0402FR-0733RL"))
    )
    (comp (ref "TP6")
      (value "1 MM")
      (footprint "TPO_SMD_ROUND_1MM")
      (description "TPO - TEST POINT ROUND SMD PAD ONLY  - 1 MM")
      (fields
        (field (name "CREATEDBY/DATE") "Jonathan Bouchard 2018-07-17")
        (field (name "VERIFIEDBY") "Arnaud Samson 23-07-18")
      )
      (libsource (lib "GRAMS_MASTER_LIB") (part "TPO_SMD_ROUND_1MM"))
    )
    (comp (ref "TP7")
      (value "1 MM")
      (footprint "TPO_SMD_ROUND_1MM")
      (description "TPO - TEST POINT ROUND SMD PAD ONLY  - 1 MM")
      (fields
        (field (name "CREATEDBY/DATE") "Jonathan Bouchard 2018-07-17")
        (field (name "VERIFIEDBY") "Arnaud Samson 23-07-18")
      )
      (libsource (lib "GRAMS_MASTER_LIB") (part "TPO_SMD_ROUND_1MM"))
    )
    (comp (ref "U10")
      (value "DS90LV001TLD/NOPB")
      (footprint "COM_BUF_DS90LV001TLD/NOPB")
      (description "COM_BUF - ReDriver 1 Channel 800Mbps CML,LVDS,LVPECL to LVDS -  \r\n8-WFDFN EP")
      (fields
        (field (name "CREATEDBY/DATE") "Louis-Daniel Gaulin / 07-04-2021")
        (field (name "VERIFIEDBY") "Philippe Arsenault/2021-04-08")
      )
      (libsource (lib "SWARMUS_LIB") (part "COM_BUF_DS90LV001TLD/NOPB"))
    )
    (comp (ref "U11")
      (value "TC7PZ05FU,LJ(CT")
      (footprint "LOG_BUF_TC7PZ05FU,LJ(CT")
      (description "LOG_BUF - DUAL Buffer inverting Open Drain - SOT-363")
      (fields
        (field (name "CREATEDBY/DATE") "Louis-Daniel Gaulin / 14-04-2021")
        (field (name "VERIFIEDBY") "Philippe Arsenault/2021-04-14")
      )
      (libsource (lib "SWARMUS_LIB") (part "LOG_BUF_TC7PZ05FU,LJ(CT"))
    )
    (comp (ref "U15")
      (value "FIN1027AMX")
      (footprint "COM_XCV_FIN1027AMCOM")
      (description "COM_XCV - 3V3 LVCMOS to LVDS, 2 bits, High-SPEED, DIFF driver - SOIC-8")
      (fields
        (field (name "CREATEDBY/DATE") "Philippe Arsenault/2021-04-01")
        (field (name "VERIFIEDBY") "Louis-Daniel Gaulin - 05/04/2021")
      )
      (libsource (lib "SWARMUS_LIB") (part "COM_XCV_FIN1027AMX"))
    )
    (comp (ref "U16")
      (value "LM339LVRTER")
      (footprint "CMP_LM339LVRTER")
      (description "COMP - Quad Comparator General Purpose Open-Drain, Rail-to-Rail - 16-WQFN (3x3)")
      (fields
        (field (name "CREATEDBY/DATE") "Philippe Arsenault/2021-04-10")
        (field (name "VERIFIEDBY") "Louis-Daniel Gaulin / 14-04-2021")
      )
      (libsource (lib "SWARMUS_LIB") (part "CMP_LM339LVRTER"))
    )
    (comp (ref "U17")
      (value "FIN1028MX")
      (footprint "COM_XCV_FIN1028MX")
      (description "COM_XCV - 3V3 LVDS to LVCMOS, 2 bits, High-SPEED, DIFF receiver - SOIC-8")
      (fields
        (field (name "CREATEDBY/DATE") "Philippe Arsenault/2021-04-01")
        (field (name "VERIFIEDBY") "Louis-Daniel Gaulin - 05/04/2021")
      )
      (libsource (lib "SWARMUS_LIB") (part "COM_XCV_FIN1028MX"))
    )
    (comp (ref "U18")
      (value "74LVC126APW,118")
      (footprint "LOG_BUF_74LVC126APW,118")
      (description "LOG_BUF - Quad Buffer non-inverting 3-States - 14-TSSOP")
      (fields
        (field (name "CREATEDBY/DATE") "Louis-Daniel Gaulin / 11-04-2021")
        (field (name "VERIFIEDBY") "Philippe Arsenault/2021-04-14")
      )
      (libsource (lib "SWARMUS_LIB") (part "LOG_BUF_74LVC126APW,118"))
    )
    (comp (ref "U19")
      (value "FIN1027AMX")
      (footprint "COM_XCV_FIN1027AMCOM")
      (description "COM_XCV - 3V3 LVCMOS to LVDS, 2 bits, High-SPEED, DIFF driver - SOIC-8")
      (fields
        (field (name "CREATEDBY/DATE") "Philippe Arsenault/2021-04-01")
        (field (name "VERIFIEDBY") "Louis-Daniel Gaulin - 05/04/2021")
      )
      (libsource (lib "SWARMUS_LIB") (part "COM_XCV_FIN1027AMX"))
    )
    (comp (ref "U20")
      (value "TC7PZ05FU,LJ(CT")
      (footprint "LOG_BUF_TC7PZ05FU,LJ(CT")
      (description "LOG_BUF - DUAL Buffer inverting Open Drain - SOT-363")
      (fields
        (field (name "CREATEDBY/DATE") "Louis-Daniel Gaulin / 14-04-2021")
        (field (name "VERIFIEDBY") "Philippe Arsenault/2021-04-14")
      )
      (libsource (lib "SWARMUS_LIB") (part "LOG_BUF_TC7PZ05FU,LJ(CT"))
    )
    (comp (ref "U21")
      (value "NIS6150MT1TXG")
      (footprint "POW_NIS6150MT1TXG")
      (description "POW -  Electronic Fuse Regulator 1A -  10-WDFNW")
      (fields
        (field (name "TOLERANCE") "See datasheet")
        (field (name "CREATEDBY/DATE") "Louis-Daniel Gaulin / 29-04-2021")
        (field (name "VERIFIEDBY") "Philippe Arsenault/2021-04-30")
      )
      (libsource (lib "SWARMUS_LIB") (part "POW_NIS6150MT1TXG"))
    )
    (comp (ref "U22")
      (value "DS90LV001TLD/NOPB")
      (footprint "COM_BUF_DS90LV001TLD/NOPB")
      (description "COM_BUF - ReDriver 1 Channel 800Mbps CML,LVDS,LVPECL to LVDS -  \r\n8-WFDFN EP")
      (fields
        (field (name "CREATEDBY/DATE") "Louis-Daniel Gaulin / 07-04-2021")
        (field (name "VERIFIEDBY") "Philippe Arsenault/2021-04-08")
      )
      (libsource (lib "SWARMUS_LIB") (part "COM_BUF_DS90LV001TLD/NOPB"))
    )
    (comp (ref "U23")
      (value "74LVC1G11DW-7")
      (footprint "LOG_AND_74LVC1G11DW-7")
      (description "LOG - AND Gate, 1CH 3-INP - 6-TSSOP")
      (fields
        (field (name "CREATEDBY/DATE") "Louis-Daniel Gaulin / 26-02-2020")
        (field (name "VERIFIEDBY") "C.Paulin - 9/03/2020")
      )
      (libsource (lib "GRAMS_MASTER_LIB") (part "LOG_AND_74LVC1G11DW-7"))
    )
    (comp (ref "U25")
      (value "74LVC1G11DW-7")
      (footprint "LOG_AND_74LVC1G11DW-7")
      (description "LOG - AND Gate, 1CH 3-INP - 6-TSSOP")
      (fields
        (field (name "CREATEDBY/DATE") "Louis-Daniel Gaulin / 26-02-2020")
        (field (name "VERIFIEDBY") "C.Paulin - 9/03/2020")
      )
      (libsource (lib "GRAMS_MASTER_LIB") (part "LOG_AND_74LVC1G11DW-7"))
    )
    (comp (ref "U27")
      (value "NIS6150MT1TXG")
      (footprint "POW_NIS6150MT1TXG")
      (description "POW -  Electronic Fuse Regulator 1A -  10-WDFNW")
      (fields
        (field (name "TOLERANCE") "See datasheet")
        (field (name "CREATEDBY/DATE") "Louis-Daniel Gaulin / 29-04-2021")
        (field (name "VERIFIEDBY") "Philippe Arsenault/2021-04-30")
      )
      (libsource (lib "SWARMUS_LIB") (part "POW_NIS6150MT1TXG"))
    )
    (comp (ref "U28")
      (value "74AHC1G07GV,125")
      (footprint "LOG_BUF_ 74AHC1G07GV,125")
      (description "LOG_BUF - Buffer non-inverting Open Drain - SC-74A")
      (fields
        (field (name "CREATEDBY/DATE") "Louis-Daniel Gaulin / 07-04-2021")
        (field (name "VERIFIEDBY") "Philippe Arsenault/2021-04-08")
      )
      (libsource (lib "SWARMUS_LIB") (part "LOG_BUF_74AHC1G07GV,125"))
    )
    (comp (ref "U29")
      (value "74AHC1G07GV,125")
      (footprint "LOG_BUF_ 74AHC1G07GV,125")
      (description "LOG_BUF - Buffer non-inverting Open Drain - SC-74A")
      (fields
        (field (name "CREATEDBY/DATE") "Louis-Daniel Gaulin / 07-04-2021")
        (field (name "VERIFIEDBY") "Philippe Arsenault/2021-04-08")
      )
      (libsource (lib "SWARMUS_LIB") (part "LOG_BUF_74AHC1G07GV,125"))
    )
    (comp (ref "U34")
      (value "74LVC1G126GV,125")
      (footprint "LOG_BUF_ 74LVC1G126GV,125")
      (description "LOG_BUF - Buffer non-inverting 3-States - SC-74A")
      (fields
        (field (name "CREATEDBY/DATE") "Philippe Arsenault/2021-04-08")
        (field (name "VERIFIEDBY") "Louis-Daniel Gaulin / 11-04-2021")
      )
      (libsource (lib "SWARMUS_LIB") (part "LOG_BUF_74LVC1G126GV,125"))
    )
    (comp (ref "U35")
      (value "74LVC1G126GV,125")
      (footprint "LOG_BUF_ 74LVC1G126GV,125")
      (description "LOG_BUF - Buffer non-inverting 3-States - SC-74A")
      (fields
        (field (name "CREATEDBY/DATE") "Philippe Arsenault/2021-04-08")
        (field (name "VERIFIEDBY") "Louis-Daniel Gaulin / 11-04-2021")
      )
      (libsource (lib "SWARMUS_LIB") (part "LOG_BUF_74LVC1G126GV,125"))
    )
    (comp (ref "U36")
      (value "74LVC1G04GV")
      (footprint "LOG_INV_74LVC1G04GV")
      (description "LOG - INVERTER 1CH 1-INP - SOT-753")
      (fields
        (field (name "CREATEDBY/DATE") "Keven Deslandes - 2018-09-12")
        (field (name "VERIFIEDBY") "Caroline Paulin - 17/12/2018")
      )
      (libsource (lib "GRAMS_MASTER_LIB") (part "LOG_INV_74LVC1G04GV"))
    )
    (comp (ref "U37")
      (value "74LVC1G04GV")
      (footprint "LOG_INV_74LVC1G04GV")
      (description "LOG - INVERTER 1CH 1-INP - SOT-753")
      (fields
        (field (name "CREATEDBY/DATE") "Keven Deslandes - 2018-09-12")
        (field (name "VERIFIEDBY") "Caroline Paulin - 17/12/2018")
      )
      (libsource (lib "GRAMS_MASTER_LIB") (part "LOG_INV_74LVC1G04GV"))
    )
  )
  (nets
    (net (code "1") (name "/BB_CC1_0") (class "Default")
      (node (ref "J4") (pin "A5") (pinfunction "CC1_A5") (pintype "passive"))
      (node (ref "R95") (pin "2") (pinfunction "2_2") (pintype "passive"))
      (node (ref "U11") (pin "1") (pinfunction "1A_1") (pintype "passive"))
    )
    (net (code "2") (name "/BB_CC1_1") (class "Default")
      (node (ref "J5") (pin "A5") (pinfunction "CC1_A5") (pintype "passive"))
      (node (ref "R117") (pin "2") (pinfunction "2_2") (pintype "passive"))
      (node (ref "U20") (pin "1") (pinfunction "1A_1") (pintype "passive"))
    )
    (net (code "3") (name "/BB_CC2_0") (class "Default")
      (node (ref "J4") (pin "B5") (pinfunction "CC2_B5") (pintype "passive"))
      (node (ref "R97") (pin "1") (pinfunction "1_1") (pintype "passive"))
      (node (ref "U11") (pin "3") (pinfunction "2A_3") (pintype "passive"))
    )
    (net (code "4") (name "/BB_CC2_1") (class "Default")
      (node (ref "J5") (pin "B5") (pinfunction "CC2_B5") (pintype "passive"))
      (node (ref "R118") (pin "1") (pinfunction "1_1") (pintype "passive"))
      (node (ref "U20") (pin "3") (pinfunction "2A_3") (pintype "passive"))
    )
    (net (code "5") (name "/BB_CLK_0_N") (class "Default")
      (node (ref "D8") (pin "5") (pinfunction "IO4_5") (pintype "passive"))
      (node (ref "D8") (pin "6") (pinfunction "NC_6") (pintype "passive"))
      (node (ref "J4") (pin "A3") (pinfunction "TX1-_A3") (pintype "passive"))
      (node (ref "U10") (pin "7") (pinfunction "OUT-_7") (pintype "passive"))
    )
    (net (code "6") (name "/BB_CLK_0_P") (class "Default")
      (node (ref "D8") (pin "4") (pinfunction "IO3_4") (pintype "passive"))
      (node (ref "D8") (pin "7") (pinfunction "NC_7") (pintype "passive"))
      (node (ref "J4") (pin "A2") (pinfunction "TX1+_A2") (pintype "passive"))
      (node (ref "U10") (pin "6") (pinfunction "OUT+_6") (pintype "passive"))
    )
    (net (code "7") (name "/BB_CLK_1_N") (class "Default")
      (node (ref "D21") (pin "5") (pinfunction "IO4_5") (pintype "passive"))
      (node (ref "D21") (pin "6") (pinfunction "NC_6") (pintype "passive"))
      (node (ref "J5") (pin "A3") (pinfunction "TX1-_A3") (pintype "passive"))
      (node (ref "U22") (pin "7") (pinfunction "OUT-_7") (pintype "passive"))
    )
    (net (code "8") (name "/BB_CLK_1_P") (class "Default")
      (node (ref "D21") (pin "4") (pinfunction "IO3_4") (pintype "passive"))
      (node (ref "D21") (pin "7") (pinfunction "NC_7") (pintype "passive"))
      (node (ref "J5") (pin "A2") (pinfunction "TX1+_A2") (pintype "passive"))
      (node (ref "U22") (pin "6") (pinfunction "OUT+_6") (pintype "passive"))
    )
    (net (code "9") (name "/BB_RESET_0") (class "Default")
      (node (ref "D9") (pin "5") (pinfunction "IO4_5") (pintype "passive"))
      (node (ref "D9") (pin "6") (pinfunction "NC_6") (pintype "passive"))
      (node (ref "J4") (pin "A8") (pinfunction "SBU1_A8") (pintype "passive"))
      (node (ref "R99") (pin "2") (pinfunction "2_2") (pintype "passive"))
      (node (ref "U16") (pin "9") (pinfunction "IN4-_9") (pintype "passive"))
      (node (ref "U18") (pin "6") (pinfunction "2Y_6") (pintype "passive"))
    )
    (net (code "10") (name "/BB_RESET_1") (class "Default")
      (node (ref "D15") (pin "5") (pinfunction "IO4_5") (pintype "passive"))
      (node (ref "D15") (pin "6") (pinfunction "NC_6") (pintype "passive"))
      (node (ref "J5") (pin "A8") (pinfunction "SBU1_A8") (pintype "passive"))
      (node (ref "R119") (pin "2") (pinfunction "2_2") (pintype "passive"))
      (node (ref "U16") (pin "2") (pinfunction "IN1-_2") (pintype "passive"))
      (node (ref "U18") (pin "11") (pinfunction "4Y_11") (pintype "passive"))
    )
    (net (code "11") (name "/BB_SPI_CLK_0_N") (class "Default")
      (node (ref "D8") (pin "1") (pinfunction "IO1_1") (pintype "passive"))
      (node (ref "D8") (pin "10") (pinfunction "NC_10") (pintype "passive"))
      (node (ref "J4") (pin "B10") (pinfunction "RX1-_B10") (pintype "passive"))
      (node (ref "U15") (pin "5") (pinfunction "Dout_2-_5") (pintype "passive"))
    )
    (net (code "12") (name "/BB_SPI_CLK_0_P") (class "Default")
      (node (ref "D8") (pin "2") (pinfunction "IO2_2") (pintype "passive"))
      (node (ref "D8") (pin "9") (pinfunction "NC_9") (pintype "passive"))
      (node (ref "J4") (pin "B11") (pinfunction "RX1+_B11") (pintype "passive"))
      (node (ref "U15") (pin "6") (pinfunction "Dout_2+_6") (pintype "passive"))
    )
    (net (code "13") (name "/BB_SPI_CLK_1_N") (class "Default")
      (node (ref "D21") (pin "1") (pinfunction "IO1_1") (pintype "passive"))
      (node (ref "D21") (pin "10") (pinfunction "NC_10") (pintype "passive"))
      (node (ref "J5") (pin "B10") (pinfunction "RX1-_B10") (pintype "passive"))
      (node (ref "U19") (pin "5") (pinfunction "Dout_2-_5") (pintype "passive"))
    )
    (net (code "14") (name "/BB_SPI_CLK_1_P") (class "Default")
      (node (ref "D21") (pin "2") (pinfunction "IO2_2") (pintype "passive"))
      (node (ref "D21") (pin "9") (pinfunction "NC_9") (pintype "passive"))
      (node (ref "J5") (pin "B11") (pinfunction "RX1+_B11") (pintype "passive"))
      (node (ref "U19") (pin "6") (pinfunction "Dout_2+_6") (pintype "passive"))
    )
    (net (code "15") (name "/BB_SPI_MISO_0_N") (class "Default")
      (node (ref "D9") (pin "2") (pinfunction "IO2_2") (pintype "passive"))
      (node (ref "D9") (pin "9") (pinfunction "NC_9") (pintype "passive"))
      (node (ref "J4") (pin "A7") (pinfunction "D-_A7") (pintype "passive"))
      (node (ref "J4") (pin "B7") (pinfunction "D-_B7") (pintype "passive"))
      (node (ref "R104") (pin "1") (pinfunction "1_1") (pintype "passive"))
      (node (ref "U17") (pin "4") (pinfunction "Rin_2-_4") (pintype "passive"))
    )
    (net (code "16") (name "/BB_SPI_MISO_0_P") (class "Default")
      (node (ref "D9") (pin "1") (pinfunction "IO1_1") (pintype "passive"))
      (node (ref "D9") (pin "10") (pinfunction "NC_10") (pintype "passive"))
      (node (ref "J4") (pin "A6") (pinfunction "D+_A6") (pintype "passive"))
      (node (ref "J4") (pin "B6") (pinfunction "D+_B6") (pintype "passive"))
      (node (ref "R104") (pin "2") (pinfunction "2_2") (pintype "passive"))
      (node (ref "U17") (pin "3") (pinfunction "Rin_2+_3") (pintype "passive"))
    )
    (net (code "17") (name "/BB_SPI_MISO_1_N") (class "Default")
      (node (ref "D15") (pin "2") (pinfunction "IO2_2") (pintype "passive"))
      (node (ref "D15") (pin "9") (pinfunction "NC_9") (pintype "passive"))
      (node (ref "J5") (pin "A7") (pinfunction "D-_A7") (pintype "passive"))
      (node (ref "J5") (pin "B7") (pinfunction "D-_B7") (pintype "passive"))
      (node (ref "R103") (pin "2") (pinfunction "2_2") (pintype "passive"))
      (node (ref "U17") (pin "1") (pinfunction "Rin_1-_1") (pintype "passive"))
    )
    (net (code "18") (name "/BB_SPI_MISO_1_P") (class "Default")
      (node (ref "D15") (pin "1") (pinfunction "IO1_1") (pintype "passive"))
      (node (ref "D15") (pin "10") (pinfunction "NC_10") (pintype "passive"))
      (node (ref "J5") (pin "A6") (pinfunction "D+_A6") (pintype "passive"))
      (node (ref "J5") (pin "B6") (pinfunction "D+_B6") (pintype "passive"))
      (node (ref "R103") (pin "1") (pinfunction "1_1") (pintype "passive"))
      (node (ref "U17") (pin "2") (pinfunction "Rin_1+_2") (pintype "passive"))
    )
    (net (code "19") (name "/BB_SPI_MOSI_0_N") (class "Default")
      (node (ref "D10") (pin "1") (pinfunction "IO1_1") (pintype "passive"))
      (node (ref "D10") (pin "10") (pinfunction "NC_10") (pintype "passive"))
      (node (ref "J4") (pin "A10") (pinfunction "RX2-_A10") (pintype "passive"))
      (node (ref "U15") (pin "7") (pinfunction "Dout_1-_7") (pintype "passive"))
    )
    (net (code "20") (name "/BB_SPI_MOSI_0_P") (class "Default")
      (node (ref "D10") (pin "2") (pinfunction "IO2_2") (pintype "passive"))
      (node (ref "D10") (pin "9") (pinfunction "NC_9") (pintype "passive"))
      (node (ref "J4") (pin "A11") (pinfunction "RX2+_A11") (pintype "passive"))
      (node (ref "U15") (pin "8") (pinfunction "Dout_1+_8") (pintype "passive"))
    )
    (net (code "21") (name "/BB_SPI_MOSI_1_N") (class "Default")
      (node (ref "D18") (pin "1") (pinfunction "IO1_1") (pintype "passive"))
      (node (ref "D18") (pin "10") (pinfunction "NC_10") (pintype "passive"))
      (node (ref "J5") (pin "A10") (pinfunction "RX2-_A10") (pintype "passive"))
      (node (ref "U19") (pin "7") (pinfunction "Dout_1-_7") (pintype "passive"))
    )
    (net (code "22") (name "/BB_SPI_MOSI_1_P") (class "Default")
      (node (ref "D18") (pin "2") (pinfunction "IO2_2") (pintype "passive"))
      (node (ref "D18") (pin "9") (pinfunction "NC_9") (pintype "passive"))
      (node (ref "J5") (pin "A11") (pinfunction "RX2+_A11") (pintype "passive"))
      (node (ref "U19") (pin "8") (pinfunction "Dout_1+_8") (pintype "passive"))
    )
    (net (code "23") (name "/BB_SPI_nCS_0") (class "Default")
      (node (ref "D9") (pin "4") (pinfunction "IO3_4") (pintype "passive"))
      (node (ref "D9") (pin "7") (pinfunction "NC_7") (pintype "passive"))
      (node (ref "J4") (pin "B8") (pinfunction "SBU2_B8") (pintype "passive"))
      (node (ref "U18") (pin "3") (pinfunction "1Y_3") (pintype "passive"))
    )
    (net (code "24") (name "/BB_SPI_nCS_1") (class "Default")
      (node (ref "D15") (pin "4") (pinfunction "IO3_4") (pintype "passive"))
      (node (ref "D15") (pin "7") (pinfunction "NC_7") (pintype "passive"))
      (node (ref "J5") (pin "B8") (pinfunction "SBU2_B8") (pintype "passive"))
      (node (ref "U18") (pin "8") (pinfunction "3Y_8") (pintype "passive"))
    )
    (net (code "25") (name "/BB_VIN_0") (class "Default")
      (node (ref "C141") (pin "2") (pinfunction "2_2") (pintype "passive"))
      (node (ref "D11") (pin "1") (pinfunction "1_1") (pintype "passive"))
      (node (ref "J4") (pin "A4") (pinfunction "VBUS_A4") (pintype "passive"))
      (node (ref "J4") (pin "A9") (pinfunction "VBUS_A9") (pintype "passive"))
      (node (ref "J4") (pin "B4") (pinfunction "VBUS_B4") (pintype "passive"))
      (node (ref "J4") (pin "B9") (pinfunction "VBUS_B9") (pintype "passive"))
      (node (ref "R151") (pin "1") (pinfunction "1_1") (pintype "passive"))
      (node (ref "TP6") (pin "1") (pinfunction "1_1") (pintype "passive"))
      (node (ref "U27") (pin "10") (pinfunction "Source_10") (pintype "passive"))
      (node (ref "U27") (pin "9") (pinfunction "Source_9") (pintype "passive"))
    )
    (net (code "26") (name "/BB_VIN_1") (class "Default")
      (node (ref "C127") (pin "2") (pinfunction "2_2") (pintype "passive"))
      (node (ref "D16") (pin "1") (pinfunction "1_1") (pintype "passive"))
      (node (ref "J5") (pin "A4") (pinfunction "VBUS_A4") (pintype "passive"))
      (node (ref "J5") (pin "A9") (pinfunction "VBUS_A9") (pintype "passive"))
      (node (ref "J5") (pin "B4") (pinfunction "VBUS_B4") (pintype "passive"))
      (node (ref "J5") (pin "B9") (pinfunction "VBUS_B9") (pintype "passive"))
      (node (ref "R152") (pin "1") (pinfunction "1_1") (pintype "passive"))
      (node (ref "TP7") (pin "1") (pinfunction "1_1") (pintype "passive"))
      (node (ref "U21") (pin "10") (pinfunction "Source_10") (pintype "passive"))
      (node (ref "U21") (pin "9") (pinfunction "Source_9") (pintype "passive"))
    )
    (net (code "27") (name "/CHAN_DET_0") (class "Default")
      (node (ref "R113") (pin "2") (pinfunction "2_2") (pintype "passive"))
      (node (ref "U16") (pin "13") (pinfunction "OUT4_13") (pintype "passive"))
    )
    (net (code "28") (name "/CHAN_DET_1") (class "Default")
      (node (ref "R124") (pin "2") (pinfunction "2_2") (pintype "passive"))
      (node (ref "U16") (pin "16") (pinfunction "OUT1_16") (pintype "passive"))
    )
    (net (code "29") (name "/CHAN_EN_0") (class "Default")
      (node (ref "U23") (pin "6") (pinfunction "C_6") (pintype "passive"))
    )
    (net (code "30") (name "/CHAN_EN_1") (class "Default")
      (node (ref "U25") (pin "6") (pinfunction "C_6") (pintype "passive"))
    )
    (net (code "31") (name "/CHAN_FLAG_0") (class "Default")
      (node (ref "U27") (pin "6") (pinfunction "FLAG_6") (pintype "passive"))
      (node (ref "U28") (pin "2") (pinfunction "A_2") (pintype "passive"))
    )
    (net (code "32") (name "/CHAN_FLAG_1") (class "Default")
      (node (ref "U21") (pin "6") (pinfunction "FLAG_6") (pintype "passive"))
      (node (ref "U29") (pin "2") (pinfunction "A_2") (pintype "passive"))
    )
    (net (code "33") (name "/CHAN_FLT#_0") (class "Default")
      (node (ref "D14") (pin "K") (pinfunction "K_K") (pintype "passive"))
      (node (ref "U28") (pin "4") (pinfunction "Y_4") (pintype "passive"))
    )
    (net (code "34") (name "/CHAN_FLT#_1") (class "Default")
      (node (ref "D20") (pin "K") (pinfunction "K_K") (pintype "passive"))
      (node (ref "U29") (pin "4") (pinfunction "Y_4") (pintype "passive"))
    )
    (net (code "35") (name "/CHAN_IRQ_0") (class "Default")
      (node (ref "R93") (pin "2") (pinfunction "2_2") (pintype "passive"))
      (node (ref "U11") (pin "4") (pinfunction "2Y_4") (pintype "passive"))
      (node (ref "U11") (pin "6") (pinfunction "1Y_6") (pintype "passive"))
    )
    (net (code "36") (name "/CHAN_IRQ_1") (class "Default")
      (node (ref "R112") (pin "2") (pinfunction "2_2") (pintype "passive"))
      (node (ref "U20") (pin "4") (pinfunction "2Y_4") (pintype "passive"))
      (node (ref "U20") (pin "6") (pinfunction "1Y_6") (pintype "passive"))
    )
    (net (code "37") (name "/CHAN_OV_0") (class "Default")
      (node (ref "R105") (pin "2") (pinfunction "2_2") (pintype "passive"))
      (node (ref "R111") (pin "2") (pinfunction "2_2") (pintype "passive"))
      (node (ref "U23") (pin "3") (pinfunction "B_3") (pintype "passive"))
    )
    (net (code "38") (name "/CHAN_OV_1") (class "Default")
      (node (ref "R101") (pin "2") (pinfunction "2_2") (pintype "passive"))
      (node (ref "R102") (pin "2") (pinfunction "2_2") (pintype "passive"))
      (node (ref "U25") (pin "3") (pinfunction "B_3") (pintype "passive"))
    )
    (net (code "39") (name "/CHAN_RESET_0") (class "Default")
      (node (ref "U18") (pin "5") (pinfunction "2A_5") (pintype "passive"))
    )
    (net (code "40") (name "/CHAN_RESET_1") (class "Default")
      (node (ref "U18") (pin "12") (pinfunction "4A_12") (pintype "passive"))
    )
    (net (code "41") (name "/CLK_0_N") (class "Default")
      (node (ref "R94") (pin "1") (pinfunction "1_1") (pintype "passive"))
      (node (ref "U10") (pin "2") (pinfunction "IN-_2") (pintype "passive"))
    )
    (net (code "42") (name "/CLK_0_P") (class "Default")
      (node (ref "R94") (pin "2") (pinfunction "2_2") (pintype "passive"))
      (node (ref "U10") (pin "3") (pinfunction "IN+_3") (pintype "passive"))
    )
    (net (code "43") (name "/CLK_1_N") (class "Default")
      (node (ref "R128") (pin "1") (pinfunction "1_1") (pintype "passive"))
      (node (ref "U22") (pin "2") (pinfunction "IN-_2") (pintype "passive"))
    )
    (net (code "44") (name "/CLK_1_P") (class "Default")
      (node (ref "R128") (pin "2") (pinfunction "2_2") (pintype "passive"))
      (node (ref "U22") (pin "3") (pinfunction "IN+_3") (pintype "passive"))
    )
    (net (code "45") (name "/HW_EN_0") (class "Default")
      (node (ref "Q3") (pin "1") (pinfunction "G_1") (pintype "passive"))
      (node (ref "U10") (pin "8") (pinfunction "EN_8") (pintype "passive"))
      (node (ref "U18") (pin "1") (pinfunction "1OE_1") (pintype "passive"))
      (node (ref "U18") (pin "4") (pinfunction "2OE_4") (pintype "passive"))
      (node (ref "U23") (pin "4") (pinfunction "Y_4") (pintype "passive"))
      (node (ref "U27") (pin "7") (pinfunction "EN_7") (pintype "passive"))
    )
    (net (code "46") (name "/HW_EN_1") (class "Default")
      (node (ref "Q4") (pin "1") (pinfunction "G_1") (pintype "passive"))
      (node (ref "U18") (pin "10") (pinfunction "3OE_10") (pintype "passive"))
      (node (ref "U18") (pin "13") (pinfunction "4OE_13") (pintype "passive"))
      (node (ref "U21") (pin "7") (pinfunction "EN_7") (pintype "passive"))
      (node (ref "U22") (pin "8") (pinfunction "EN_8") (pintype "passive"))
      (node (ref "U25") (pin "4") (pinfunction "Y_4") (pintype "passive"))
    )
    (net (code "47") (name "/SPI_CLK") (class "Default")
      (node (ref "U15") (pin "3") (pinfunction "Din_2_3") (pintype "passive"))
      (node (ref "U19") (pin "3") (pinfunction "Din_2_3") (pintype "passive"))
    )
    (net (code "48") (name "/SPI_CS_0") (class "Default")
      (node (ref "U35") (pin "1") (pinfunction "OE_1") (pintype "passive"))
      (node (ref "U37") (pin "4") (pinfunction "Y_4") (pintype "passive"))
    )
    (net (code "49") (name "/SPI_CS_1") (class "Default")
      (node (ref "U34") (pin "1") (pinfunction "OE_1") (pintype "passive"))
      (node (ref "U36") (pin "4") (pinfunction "Y_4") (pintype "passive"))
    )
    (net (code "50") (name "/SPI_MISO") (class "Default")
      (node (ref "R164") (pin "2") (pinfunction "2_2") (pintype "passive"))
      (node (ref "R174") (pin "2") (pinfunction "2_2") (pintype "passive"))
    )
    (net (code "51") (name "/SPI_MISO_0") (class "Default")
      (node (ref "U17") (pin "6") (pinfunction "Rout_2_6") (pintype "passive"))
      (node (ref "U35") (pin "2") (pinfunction "A_2") (pintype "passive"))
    )
    (net (code "52") (name "/SPI_MISO_1") (class "Default")
      (node (ref "U17") (pin "7") (pinfunction "Rout_1_7") (pintype "passive"))
      (node (ref "U34") (pin "2") (pinfunction "A_2") (pintype "passive"))
    )
    (net (code "53") (name "/SPI_MOSI") (class "Default")
      (node (ref "U15") (pin "2") (pinfunction "Din_1_2") (pintype "passive"))
      (node (ref "U19") (pin "2") (pinfunction "Din_1_2") (pintype "passive"))
    )
    (net (code "54") (name "/SPI_nCS_0") (class "Default")
      (node (ref "U18") (pin "2") (pinfunction "1A_2") (pintype "passive"))
      (node (ref "U37") (pin "2") (pinfunction "A_2") (pintype "passive"))
    )
    (net (code "55") (name "/SPI_nCS_1") (class "Default")
      (node (ref "U18") (pin "9") (pinfunction "3A_9") (pintype "passive"))
      (node (ref "U36") (pin "2") (pinfunction "A_2") (pintype "passive"))
    )
    (net (code "56") (name "/SYNC_0_N") (class "Default")
      (node (ref "D10") (pin "5") (pinfunction "IO4_5") (pintype "passive"))
      (node (ref "D10") (pin "6") (pinfunction "NC_6") (pintype "passive"))
      (node (ref "J4") (pin "B3") (pinfunction "TX2-_B3") (pintype "passive"))
    )
    (net (code "57") (name "/SYNC_0_P") (class "Default")
      (node (ref "D10") (pin "4") (pinfunction "IO3_4") (pintype "passive"))
      (node (ref "D10") (pin "7") (pinfunction "NC_7") (pintype "passive"))
      (node (ref "J4") (pin "B2") (pinfunction "TX2+_B2") (pintype "passive"))
    )
    (net (code "58") (name "/SYNC_1_N") (class "Default")
      (node (ref "D18") (pin "5") (pinfunction "IO4_5") (pintype "passive"))
      (node (ref "D18") (pin "6") (pinfunction "NC_6") (pintype "passive"))
      (node (ref "J5") (pin "B3") (pinfunction "TX2-_B3") (pintype "passive"))
    )
    (net (code "59") (name "/SYNC_1_P") (class "Default")
      (node (ref "D18") (pin "4") (pinfunction "IO3_4") (pintype "passive"))
      (node (ref "D18") (pin "7") (pinfunction "NC_7") (pintype "passive"))
      (node (ref "J5") (pin "B2") (pinfunction "TX2+_B2") (pintype "passive"))
    )
    (net (code "60") (name "3V3") (class "Default")
      (node (ref "C117") (pin "2") (pinfunction "2_2") (pintype "passive"))
      (node (ref "C128") (pin "2") (pinfunction "2_2") (pintype "passive"))
      (node (ref "C133") (pin "2") (pinfunction "2_2") (pintype "passive"))
      (node (ref "R100") (pin "1") (pinfunction "1_1") (pintype "passive"))
      (node (ref "R101") (pin "1") (pinfunction "1_1") (pintype "passive"))
      (node (ref "R110") (pin "2") (pinfunction "2_2") (pintype "passive"))
      (node (ref "R111") (pin "1") (pinfunction "1_1") (pintype "passive"))
      (node (ref "R113") (pin "1") (pinfunction "1_1") (pintype "passive"))
      (node (ref "R115") (pin "2") (pinfunction "2_2") (pintype "passive"))
      (node (ref "R123") (pin "2") (pinfunction "2_2") (pintype "passive"))
      (node (ref "R124") (pin "1") (pinfunction "1_1") (pintype "passive"))
      (node (ref "R77") (pin "2") (pinfunction "2_2") (pintype "passive"))
      (node (ref "U16") (pin "1") (pinfunction "V+_1") (pintype "passive"))
      (node (ref "U23") (pin "5") (pinfunction "VCC_5") (pintype "passive"))
      (node (ref "U25") (pin "5") (pinfunction "VCC_5") (pintype "passive"))
    )
    (net (code "61") (name "3V3_CH") (class "Default")
      (node (ref "C108") (pin "2") (pinfunction "2_2") (pintype "passive"))
      (node (ref "C109") (pin "2") (pinfunction "2_2") (pintype "passive"))
      (node (ref "C110") (pin "1") (pinfunction "1_1") (pintype "passive"))
      (node (ref "C113") (pin "2") (pinfunction "2_2") (pintype "passive"))
      (node (ref "C114") (pin "1") (pinfunction "1_1") (pintype "passive"))
      (node (ref "C115") (pin "1") (pinfunction "1_1") (pintype "passive"))
      (node (ref "C118") (pin "1") (pinfunction "1_1") (pintype "passive"))
      (node (ref "C119") (pin "1") (pinfunction "1_1") (pintype "passive"))
      (node (ref "C120") (pin "1") (pinfunction "1_1") (pintype "passive"))
      (node (ref "C121") (pin "1") (pinfunction "1_1") (pintype "passive"))
      (node (ref "C122") (pin "1") (pinfunction "1_1") (pintype "passive"))
      (node (ref "C125") (pin "2") (pinfunction "2_2") (pintype "passive"))
      (node (ref "C126") (pin "2") (pinfunction "2_2") (pintype "passive"))
      (node (ref "C145") (pin "1") (pinfunction "1_1") (pintype "passive"))
      (node (ref "C146") (pin "1") (pinfunction "1_1") (pintype "passive"))
      (node (ref "C150") (pin "1") (pinfunction "1_1") (pintype "passive"))
      (node (ref "C151") (pin "1") (pinfunction "1_1") (pintype "passive"))
      (node (ref "R112") (pin "1") (pinfunction "1_1") (pintype "passive"))
      (node (ref "R117") (pin "1") (pinfunction "1_1") (pintype "passive"))
      (node (ref "R119") (pin "1") (pinfunction "1_1") (pintype "passive"))
      (node (ref "R93") (pin "1") (pinfunction "1_1") (pintype "passive"))
      (node (ref "R95") (pin "1") (pinfunction "1_1") (pintype "passive"))
      (node (ref "R99") (pin "1") (pinfunction "1_1") (pintype "passive"))
      (node (ref "U10") (pin "5") (pinfunction "VCC_5") (pintype "passive"))
      (node (ref "U11") (pin "5") (pinfunction "VCC_5") (pintype "passive"))
      (node (ref "U15") (pin "1") (pinfunction "VCC_1") (pintype "passive"))
      (node (ref "U17") (pin "8") (pinfunction "VCC_8") (pintype "passive"))
      (node (ref "U18") (pin "14") (pinfunction "VCC_14") (pintype "passive"))
      (node (ref "U19") (pin "1") (pinfunction "VCC_1") (pintype "passive"))
      (node (ref "U20") (pin "5") (pinfunction "VCC_5") (pintype "passive"))
      (node (ref "U22") (pin "5") (pinfunction "VCC_5") (pintype "passive"))
      (node (ref "U23") (pin "1") (pinfunction "A_1") (pintype "passive"))
      (node (ref "U25") (pin "1") (pinfunction "A_1") (pintype "passive"))
      (node (ref "U34") (pin "5") (pinfunction "VCC_5") (pintype "passive"))
      (node (ref "U35") (pin "5") (pinfunction "VCC_5") (pintype "passive"))
      (node (ref "U36") (pin "5") (pinfunction "VCC_5") (pintype "passive"))
      (node (ref "U37") (pin "5") (pinfunction "VCC_5") (pintype "passive"))
    )
    (net (code "62") (name "5V") (class "Default")
      (node (ref "C111") (pin "1") (pinfunction "1_1") (pintype "passive"))
      (node (ref "C124") (pin "2") (pinfunction "2_2") (pintype "passive"))
      (node (ref "C139") (pin "1") (pinfunction "1_1") (pintype "passive"))
      (node (ref "C140") (pin "2") (pinfunction "2_2") (pintype "passive"))
      (node (ref "R107") (pin "1") (pinfunction "1_1") (pintype "passive"))
      (node (ref "U21") (pin "1") (pinfunction "VCC_1") (pintype "passive"))
      (node (ref "U21") (pin "2") (pinfunction "VCC_2") (pintype "passive"))
      (node (ref "U27") (pin "1") (pinfunction "VCC_1") (pintype "passive"))
      (node (ref "U27") (pin "2") (pinfunction "VCC_2") (pintype "passive"))
      (node (ref "U28") (pin "5") (pinfunction "VCC_5") (pintype "passive"))
      (node (ref "U29") (pin "5") (pinfunction "VCC_5") (pintype "passive"))
    )
    (net (code "63") (name "GND") (class "Default")
      (node (ref "C108") (pin "1") (pinfunction "1_1") (pintype "passive"))
      (node (ref "C109") (pin "1") (pinfunction "1_1") (pintype "passive"))
      (node (ref "C110") (pin "2") (pinfunction "2_2") (pintype "passive"))
      (node (ref "C111") (pin "2") (pinfunction "2_2") (pintype "passive"))
      (node (ref "C113") (pin "1") (pinfunction "1_1") (pintype "passive"))
      (node (ref "C114") (pin "2") (pinfunction "2_2") (pintype "passive"))
      (node (ref "C115") (pin "2") (pinfunction "2_2") (pintype "passive"))
      (node (ref "C117") (pin "1") (pinfunction "1_1") (pintype "passive"))
      (node (ref "C118") (pin "2") (pinfunction "2_2") (pintype "passive"))
      (node (ref "C119") (pin "2") (pinfunction "2_2") (pintype "passive"))
      (node (ref "C120") (pin "2") (pinfunction "2_2") (pintype "passive"))
      (node (ref "C121") (pin "2") (pinfunction "2_2") (pintype "passive"))
      (node (ref "C122") (pin "2") (pinfunction "2_2") (pintype "passive"))
      (node (ref "C124") (pin "1") (pinfunction "1_1") (pintype "passive"))
      (node (ref "C125") (pin "1") (pinfunction "1_1") (pintype "passive"))
      (node (ref "C126") (pin "1") (pinfunction "1_1") (pintype "passive"))
      (node (ref "C127") (pin "1") (pinfunction "1_1") (pintype "passive"))
      (node (ref "C128") (pin "1") (pinfunction "1_1") (pintype "passive"))
      (node (ref "C133") (pin "1") (pinfunction "1_1") (pintype "passive"))
      (node (ref "C139") (pin "2") (pinfunction "2_2") (pintype "passive"))
      (node (ref "C140") (pin "1") (pinfunction "1_1") (pintype "passive"))
      (node (ref "C141") (pin "1") (pinfunction "1_1") (pintype "passive"))
      (node (ref "C145") (pin "2") (pinfunction "2_2") (pintype "passive"))
      (node (ref "C146") (pin "2") (pinfunction "2_2") (pintype "passive"))
      (node (ref "C150") (pin "2") (pinfunction "2_2") (pintype "passive"))
      (node (ref "C151") (pin "2") (pinfunction "2_2") (pintype "passive"))
      (node (ref "D10") (pin "3") (pinfunction "VSS_3") (pintype "passive"))
      (node (ref "D10") (pin "8") (pinfunction "VSS_8") (pintype "passive"))
      (node (ref "D11") (pin "2") (pinfunction "2_2") (pintype "passive"))
      (node (ref "D15") (pin "3") (pinfunction "VSS_3") (pintype "passive"))
      (node (ref "D15") (pin "8") (pinfunction "VSS_8") (pintype "passive"))
      (node (ref "D16") (pin "2") (pinfunction "2_2") (pintype "passive"))
      (node (ref "D18") (pin "3") (pinfunction "VSS_3") (pintype "passive"))
      (node (ref "D18") (pin "8") (pinfunction "VSS_8") (pintype "passive"))
      (node (ref "D21") (pin "3") (pinfunction "VSS_3") (pintype "passive"))
      (node (ref "D21") (pin "8") (pinfunction "VSS_8") (pintype "passive"))
      (node (ref "D8") (pin "3") (pinfunction "VSS_3") (pintype "passive"))
      (node (ref "D8") (pin "8") (pinfunction "VSS_8") (pintype "passive"))
      (node (ref "D9") (pin "3") (pinfunction "VSS_3") (pintype "passive"))
      (node (ref "D9") (pin "8") (pinfunction "VSS_8") (pintype "passive"))
      (node (ref "J4") (pin "A1") (pinfunction "GND_A1") (pintype "passive"))
      (node (ref "J4") (pin "A12") (pinfunction "GND_A12") (pintype "passive"))
      (node (ref "J4") (pin "B1") (pinfunction "GND_B1") (pintype "passive"))
      (node (ref "J4") (pin "B12") (pinfunction "GND_B12") (pintype "passive"))
      (node (ref "J5") (pin "A1") (pinfunction "GND_A1") (pintype "passive"))
      (node (ref "J5") (pin "A12") (pinfunction "GND_A12") (pintype "passive"))
      (node (ref "J5") (pin "B1") (pinfunction "GND_B1") (pintype "passive"))
      (node (ref "J5") (pin "B12") (pinfunction "GND_B12") (pintype "passive"))
      (node (ref "Q3") (pin "2") (pinfunction "S_2") (pintype "passive"))
      (node (ref "Q4") (pin "2") (pinfunction "S_2") (pintype "passive"))
      (node (ref "R106") (pin "2") (pinfunction "2_2") (pintype "passive"))
      (node (ref "R108") (pin "1") (pinfunction "1_1") (pintype "passive"))
      (node (ref "R118") (pin "2") (pinfunction "2_2") (pintype "passive"))
      (node (ref "R127") (pin "2") (pinfunction "2_2") (pintype "passive"))
      (node (ref "R133") (pin "2") (pinfunction "2_2") (pintype "passive"))
      (node (ref "R154") (pin "1") (pinfunction "1_1") (pintype "passive"))
      (node (ref "R155") (pin "1") (pinfunction "1_1") (pintype "passive"))
      (node (ref "R97") (pin "2") (pinfunction "2_2") (pintype "passive"))
      (node (ref "U10") (pin "1") (pinfunction "GND_1") (pintype "passive"))
      (node (ref "U10") (pin "9") (pinfunction "EP_9") (pintype "passive"))
      (node (ref "U11") (pin "2") (pinfunction "GND_2") (pintype "passive"))
      (node (ref "U15") (pin "4") (pinfunction "GND_4") (pintype "passive"))
      (node (ref "U16") (pin "12") (pinfunction "GND_12") (pintype "passive"))
      (node (ref "U16") (pin "17") (pinfunction "EPAD_17") (pintype "passive"))
      (node (ref "U17") (pin "5") (pinfunction "GND_5") (pintype "passive"))
      (node (ref "U18") (pin "7") (pinfunction "GND_7") (pintype "passive"))
      (node (ref "U19") (pin "4") (pinfunction "GND_4") (pintype "passive"))
      (node (ref "U20") (pin "2") (pinfunction "GND_2") (pintype "passive"))
      (node (ref "U21") (pin "11") (pinfunction "EP_11") (pintype "passive"))
      (node (ref "U21") (pin "3") (pinfunction "GND_3") (pintype "passive"))
      (node (ref "U22") (pin "1") (pinfunction "GND_1") (pintype "passive"))
      (node (ref "U22") (pin "9") (pinfunction "EP_9") (pintype "passive"))
      (node (ref "U23") (pin "2") (pinfunction "GND_2") (pintype "passive"))
      (node (ref "U25") (pin "2") (pinfunction "GND_2") (pintype "passive"))
      (node (ref "U27") (pin "11") (pinfunction "EP_11") (pintype "passive"))
      (node (ref "U27") (pin "3") (pinfunction "GND_3") (pintype "passive"))
      (node (ref "U28") (pin "3") (pinfunction "GND_3") (pintype "passive"))
      (node (ref "U29") (pin "3") (pinfunction "GND_3") (pintype "passive"))
      (node (ref "U34") (pin "3") (pinfunction "GND_3") (pintype "passive"))
      (node (ref "U35") (pin "3") (pinfunction "GND_3") (pintype "passive"))
      (node (ref "U36") (pin "3") (pinfunction "GND_3") (pintype "passive"))
      (node (ref "U37") (pin "3") (pinfunction "GND_3") (pintype "passive"))
    )
    (net (code "64") (name "Net-(D14-PadA)") (class "Default")
      (node (ref "D14") (pin "A") (pinfunction "A_A") (pintype "passive"))
      (node (ref "R115") (pin "1") (pinfunction "1_1") (pintype "passive"))
    )
    (net (code "65") (name "Net-(D17-PadA)") (class "Default")
      (node (ref "D17") (pin "A") (pinfunction "A_A") (pintype "passive"))
      (node (ref "R77") (pin "1") (pinfunction "1_1") (pintype "passive"))
    )
    (net (code "66") (name "Net-(D19-PadA)") (class "Default")
      (node (ref "D19") (pin "A") (pinfunction "A_A") (pintype "passive"))
      (node (ref "R110") (pin "1") (pinfunction "1_1") (pintype "passive"))
    )
    (net (code "67") (name "Net-(D20-PadA)") (class "Default")
      (node (ref "D20") (pin "A") (pinfunction "A_A") (pintype "passive"))
      (node (ref "R123") (pin "1") (pinfunction "1_1") (pintype "passive"))
    )
    (net (code "68") (name "Net-(J4-Shield-Pad1)") (class "Default")
      (node (ref "J4") (pin "1") (pinfunction "Shield_1") (pintype "passive"))
      (node (ref "J4") (pin "2") (pinfunction "Shield_2") (pintype "passive"))
      (node (ref "J4") (pin "3") (pinfunction "Shield_3") (pintype "passive"))
      (node (ref "J4") (pin "4") (pinfunction "Shield_4") (pintype "passive"))
      (node (ref "R154") (pin "2") (pinfunction "2_2") (pintype "passive"))
    )
    (net (code "69") (name "Net-(J5-Shield-Pad1)") (class "Default")
      (node (ref "J5") (pin "1") (pinfunction "Shield_1") (pintype "passive"))
      (node (ref "J5") (pin "2") (pinfunction "Shield_2") (pintype "passive"))
      (node (ref "J5") (pin "3") (pinfunction "Shield_3") (pintype "passive"))
      (node (ref "J5") (pin "4") (pinfunction "Shield_4") (pintype "passive"))
      (node (ref "R155") (pin "2") (pinfunction "2_2") (pintype "passive"))
    )
    (net (code "70") (name "Net-(Q3-D)") (class "Default")
      (node (ref "D17") (pin "K") (pinfunction "K_K") (pintype "passive"))
      (node (ref "Q3") (pin "3") (pinfunction "D_3") (pintype "passive"))
    )
    (net (code "71") (name "Net-(Q4-D)") (class "Default")
      (node (ref "D19") (pin "K") (pinfunction "K_K") (pintype "passive"))
      (node (ref "Q4") (pin "3") (pinfunction "D_3") (pintype "passive"))
    )
    (net (code "72") (name "Net-(U16-IN1+)") (class "Default")
      (node (ref "R100") (pin "2") (pinfunction "2_2") (pintype "passive"))
      (node (ref "R106") (pin "1") (pinfunction "1_1") (pintype "passive"))
      (node (ref "U16") (pin "11") (pinfunction "IN4+_11") (pintype "passive"))
      (node (ref "U16") (pin "4") (pinfunction "IN1+_4") (pintype "passive"))
      (node (ref "U16") (pin "6") (pinfunction "IN2+_6") (pintype "passive"))
      (node (ref "U16") (pin "8") (pinfunction "IN3+_8") (pintype "passive"))
    )
    (net (code "73") (name "Net-(U16-IN2-)") (class "Default")
      (node (ref "R107") (pin "2") (pinfunction "2_2") (pintype "passive"))
      (node (ref "R108") (pin "2") (pinfunction "2_2") (pintype "passive"))
      (node (ref "U16") (pin "5") (pinfunction "IN2-_5") (pintype "passive"))
      (node (ref "U16") (pin "7") (pinfunction "IN3-_7") (pintype "passive"))
    )
    (net (code "74") (name "Net-(U16-OUT2)") (class "Default")
      (node (ref "R102") (pin "1") (pinfunction "1_1") (pintype "passive"))
      (node (ref "U16") (pin "15") (pinfunction "OUT2_15") (pintype "passive"))
    )
    (net (code "75") (name "Net-(U16-OUT3)") (class "Default")
      (node (ref "R105") (pin "1") (pinfunction "1_1") (pintype "passive"))
      (node (ref "U16") (pin "14") (pinfunction "OUT3_14") (pintype "passive"))
    )
    (net (code "76") (name "Net-(U21-Ilim)") (class "Default")
      (node (ref "R152") (pin "2") (pinfunction "2_2") (pintype "passive"))
      (node (ref "U21") (pin "8") (pinfunction "Ilim_8") (pintype "passive"))
    )
    (net (code "77") (name "Net-(U21-VC_SEL)") (class "Default")
      (node (ref "R127") (pin "1") (pinfunction "1_1") (pintype "passive"))
      (node (ref "U21") (pin "5") (pinfunction "VC_SEL_5") (pintype "passive"))
    )
    (net (code "78") (name "Net-(U27-Ilim)") (class "Default")
      (node (ref "R151") (pin "2") (pinfunction "2_2") (pintype "passive"))
      (node (ref "U27") (pin "8") (pinfunction "Ilim_8") (pintype "passive"))
    )
    (net (code "79") (name "Net-(U27-VC_SEL)") (class "Default")
      (node (ref "R133") (pin "1") (pinfunction "1_1") (pintype "passive"))
      (node (ref "U27") (pin "5") (pinfunction "VC_SEL_5") (pintype "passive"))
    )
    (net (code "80") (name "Net-(U34-Y)") (class "Default")
      (node (ref "R164") (pin "1") (pinfunction "1_1") (pintype "passive"))
      (node (ref "U34") (pin "4") (pinfunction "Y_4") (pintype "passive"))
    )
    (net (code "81") (name "Net-(U35-Y)") (class "Default")
      (node (ref "R174") (pin "1") (pinfunction "1_1") (pintype "passive"))
      (node (ref "U35") (pin "4") (pinfunction "Y_4") (pintype "passive"))
    )
    (net (code "82") (name "unconnected-(U10-NC-Pad4)") (class "Default")
      (node (ref "U10") (pin "4") (pinfunction "NC_4") (pintype "passive+no_connect"))
    )
    (net (code "83") (name "unconnected-(U16-NC-Pad3)") (class "Default")
      (node (ref "U16") (pin "3") (pinfunction "NC_3") (pintype "passive+no_connect"))
    )
    (net (code "84") (name "unconnected-(U16-NC-Pad10)") (class "Default")
      (node (ref "U16") (pin "10") (pinfunction "NC_10") (pintype "passive+no_connect"))
    )
    (net (code "85") (name "unconnected-(U21-IMON-Pad4)") (class "Default")
      (node (ref "U21") (pin "4") (pinfunction "IMON_4") (pintype "passive+no_connect"))
    )
    (net (code "86") (name "unconnected-(U22-NC-Pad4)") (class "Default")
      (node (ref "U22") (pin "4") (pinfunction "NC_4") (pintype "passive+no_connect"))
    )
    (net (code "87") (name "unconnected-(U27-IMON-Pad4)") (class "Default")
      (node (ref "U27") (pin "4") (pinfunction "IMON_4") (pintype "passive+no_connect"))
    )
    (net (code "88") (name "unconnected-(U28-NC-Pad1)") (class "Default")
      (node (ref "U28") (pin "1") (pinfunction "NC_1") (pintype "passive+no_connect"))
    )
    (net (code "89") (name "unconnected-(U29-NC-Pad1)") (class "Default")
      (node (ref "U29") (pin "1") (pinfunction "NC_1") (pintype "passive+no_connect"))
    )
    (net (code "90") (name "unconnected-(U36-NC-Pad1)") (class "Default")
      (node (ref "U36") (pin "1") (pinfunction "NC_1") (pintype "passive+no_connect"))
    )
    (net (code "91") (name "unconnected-(U37-NC-Pad1)") (class "Default")
      (node (ref "U37") (pin "1") (pinfunction "NC_1") (pintype "passive+no_connect"))
    )
  )
)
